# novadac.net
KiCad netlist of a schematic drawn in EasyEDA Pro
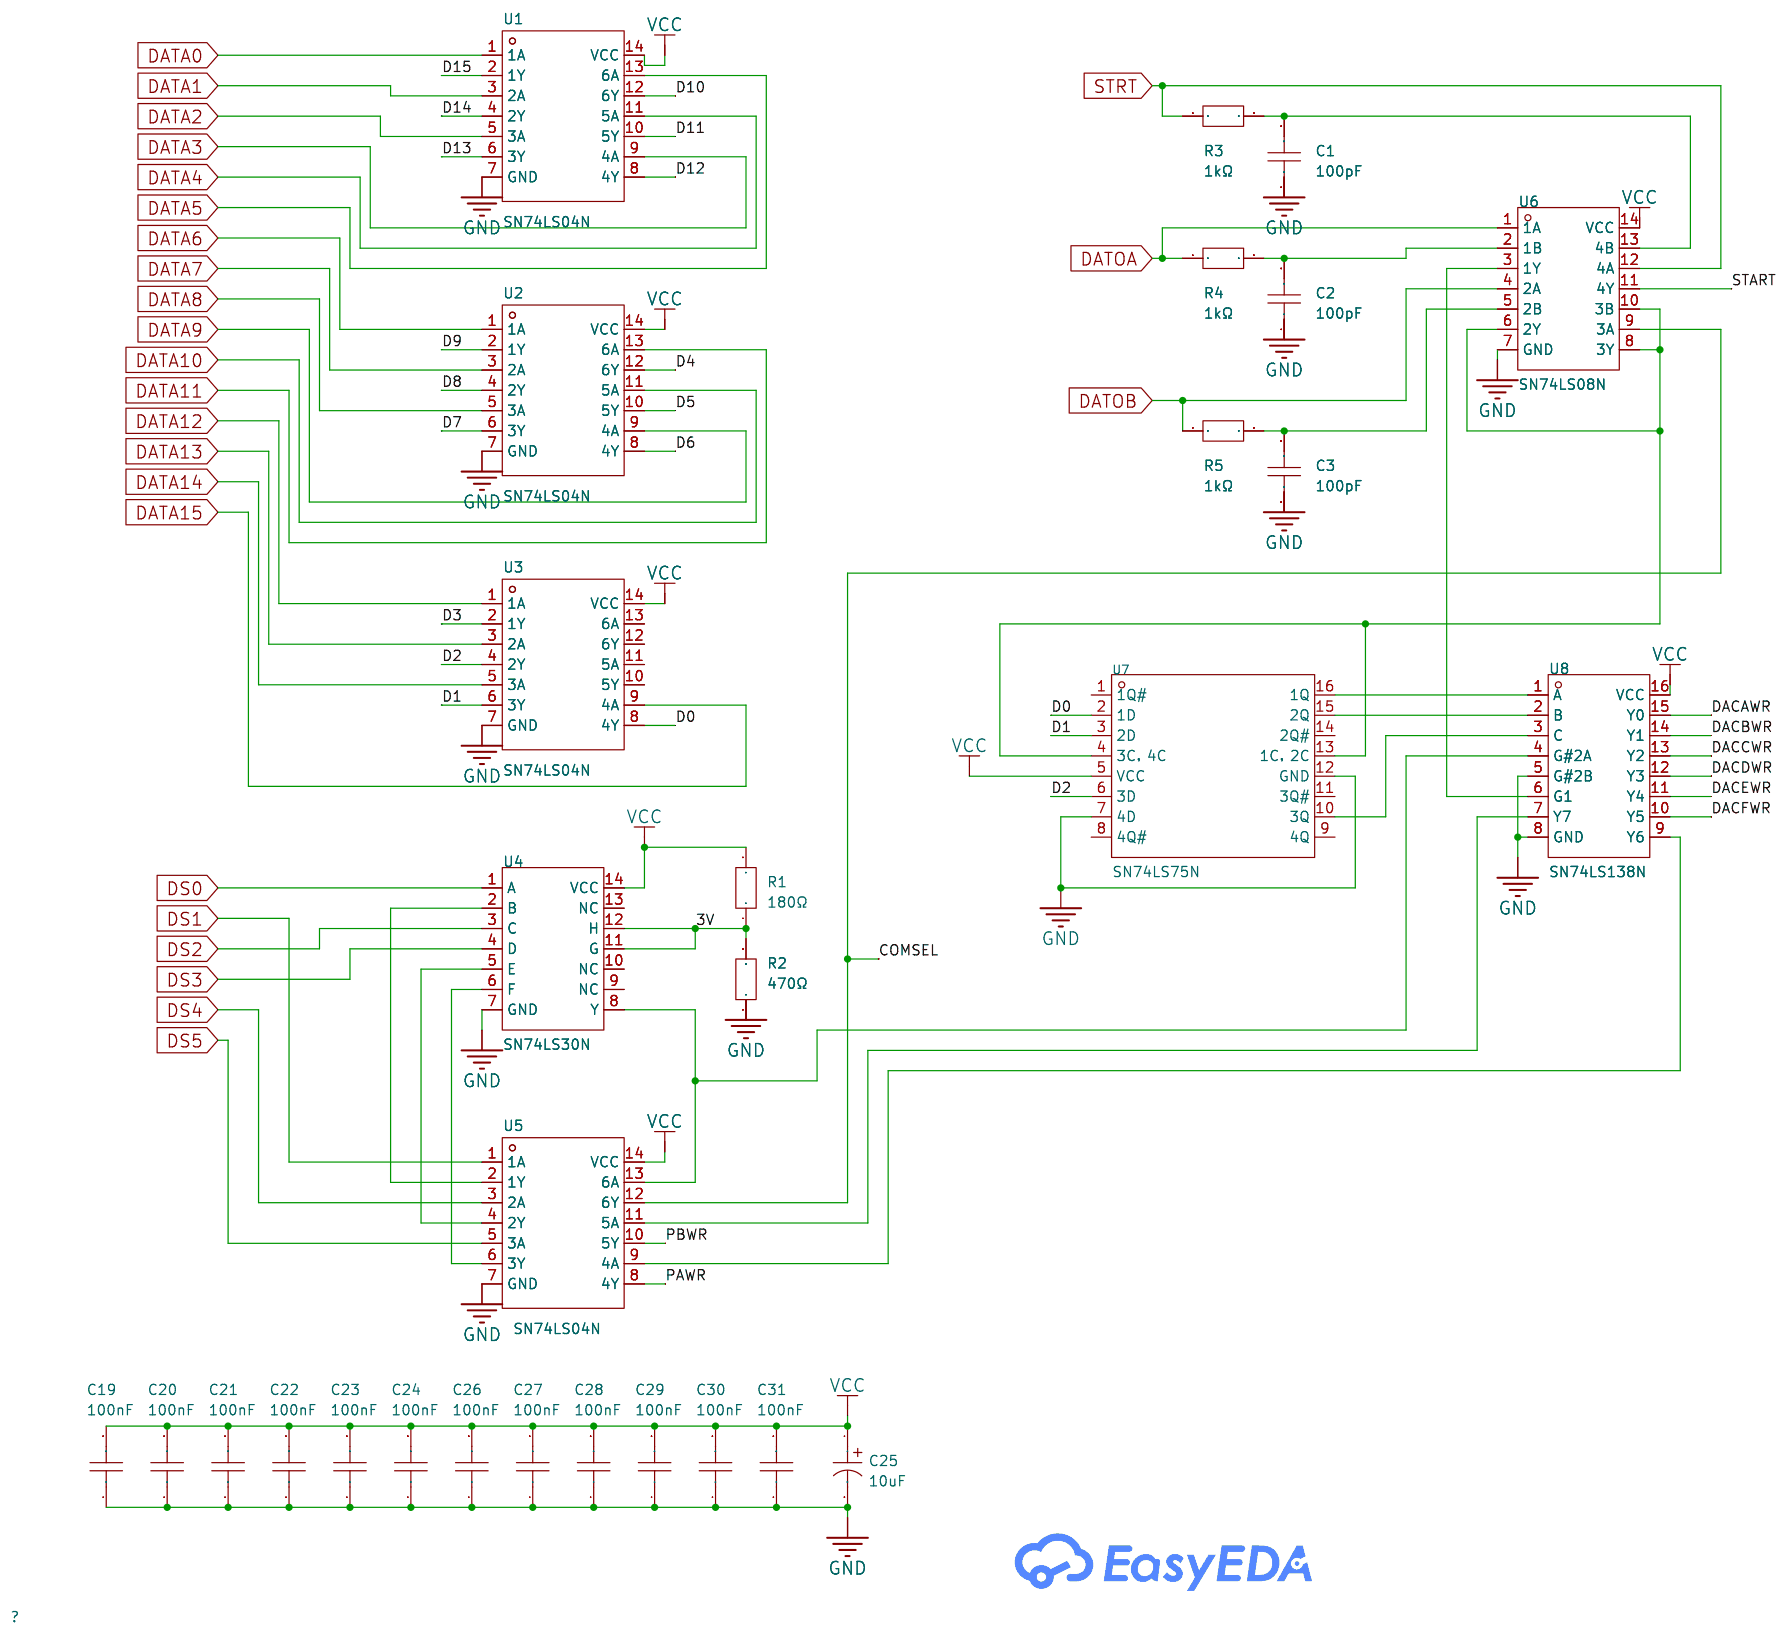
[diagram p0: P1]
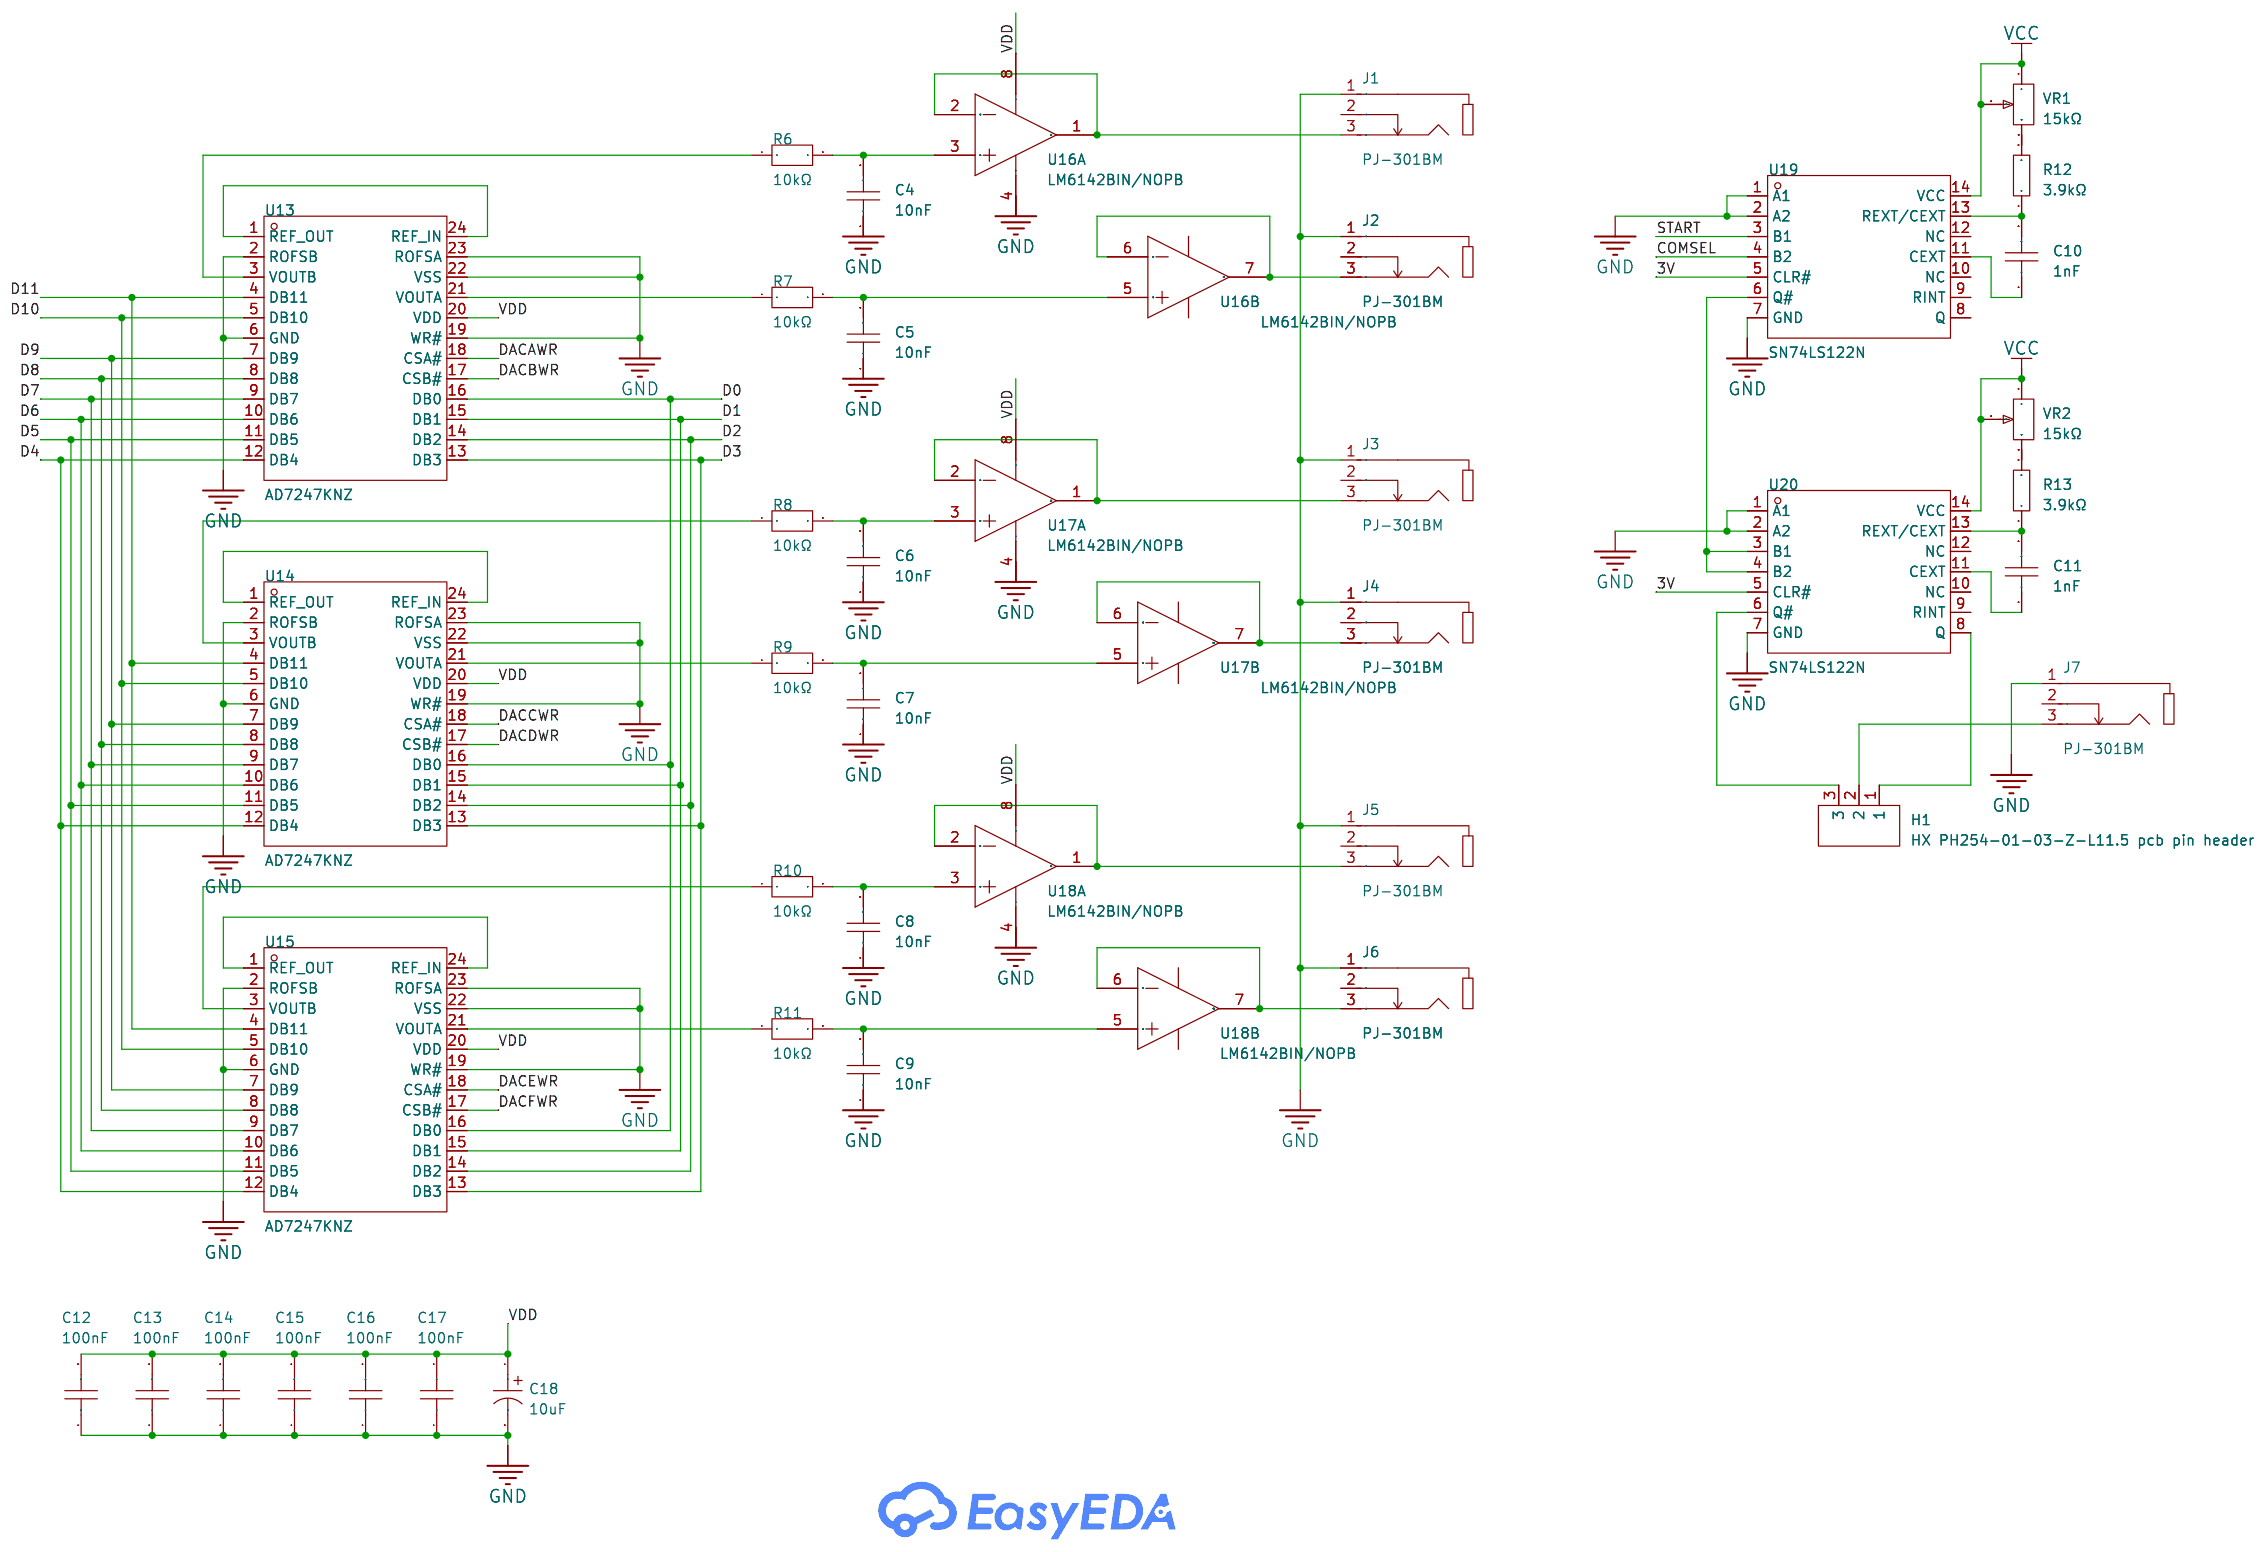
[diagram p1: P2]
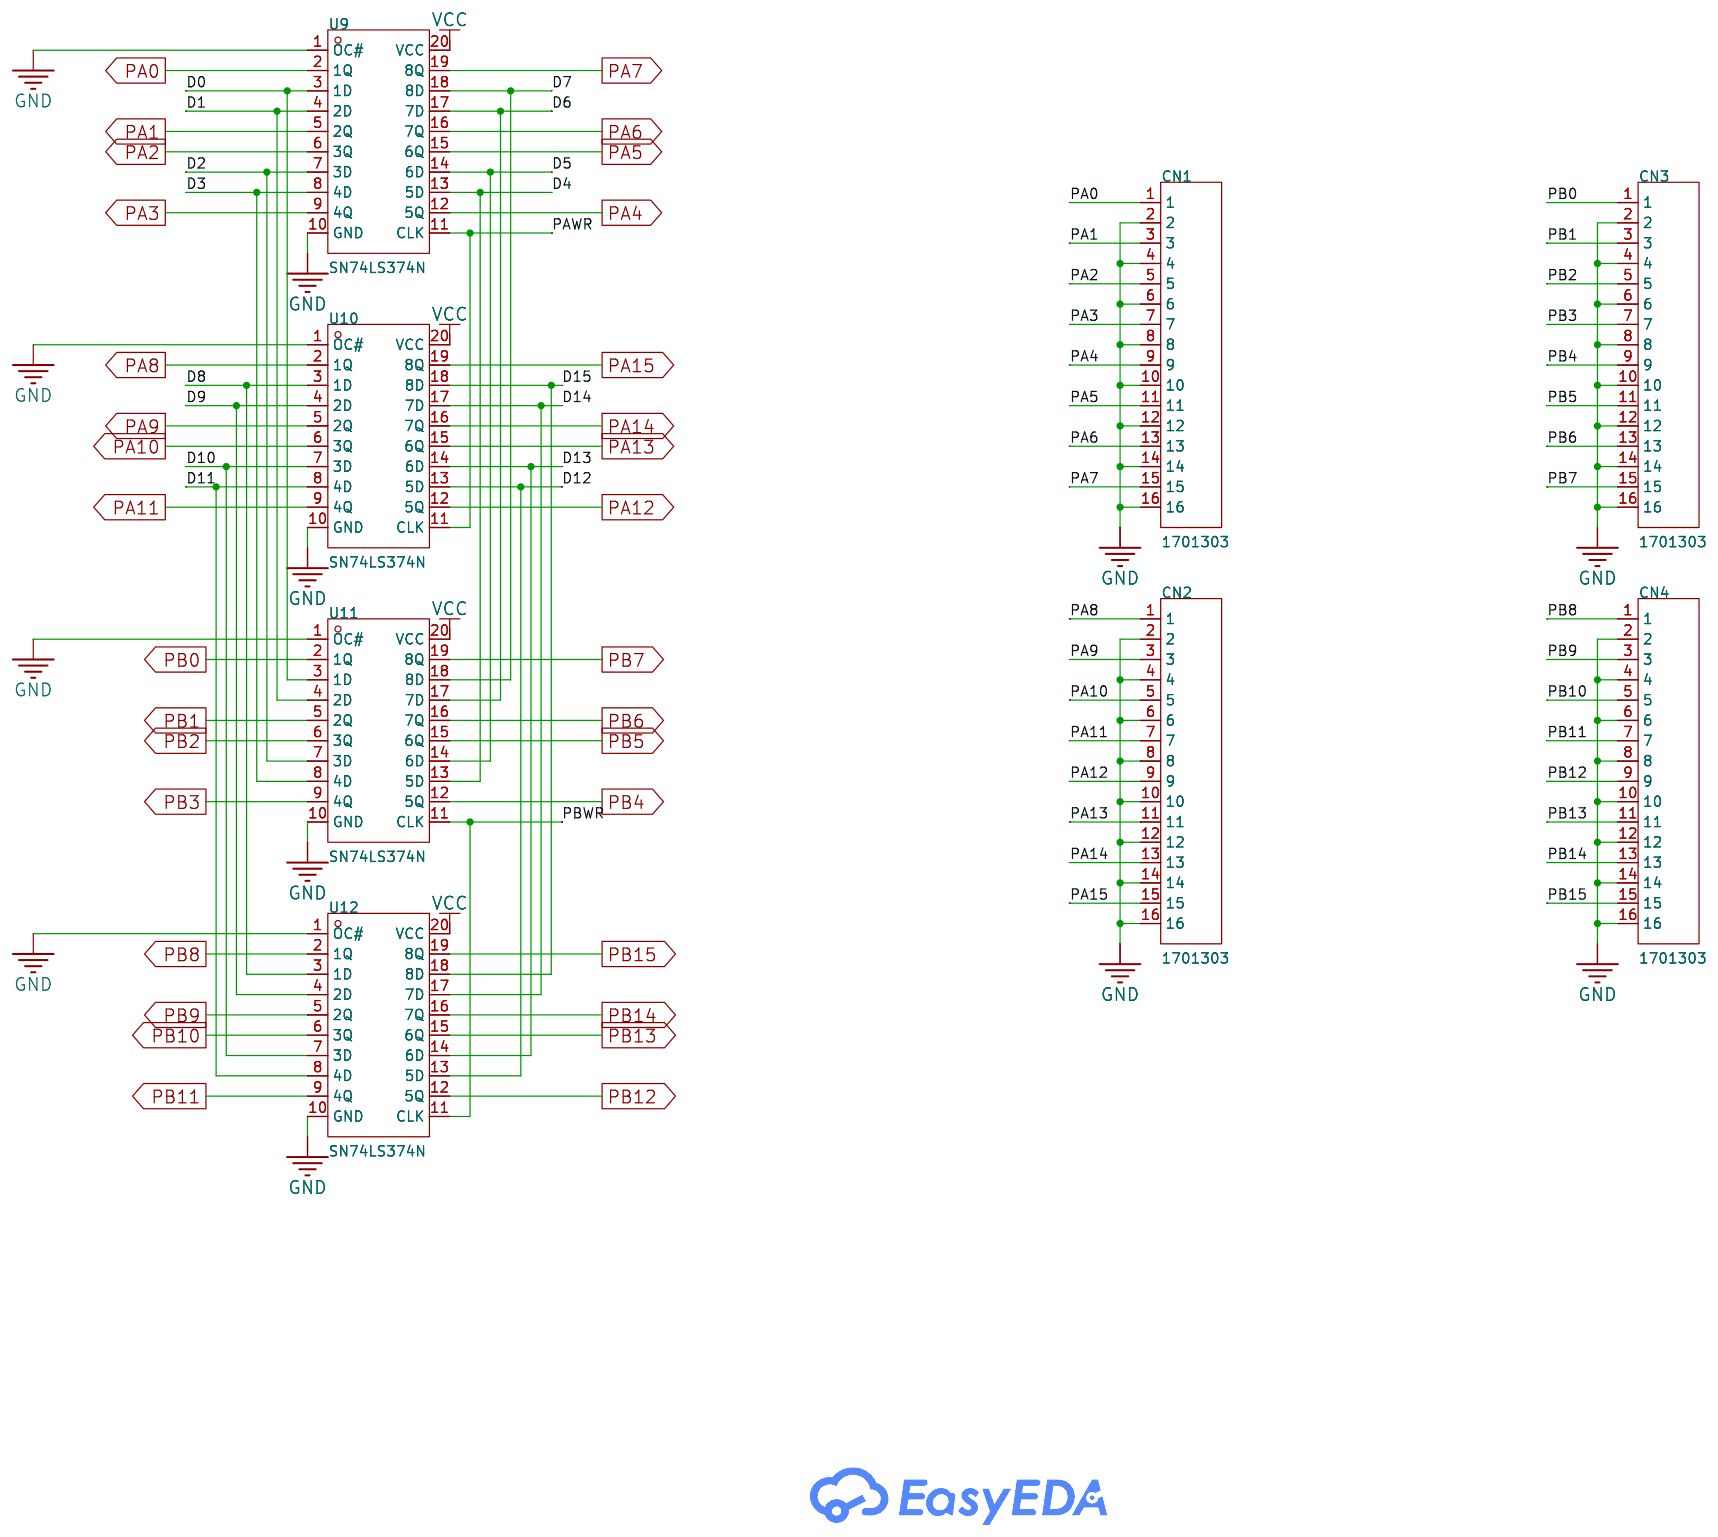
[diagram p2: P3]

(export (version "E")
  (design (tool "Eeschema 10.0.6"))
  (components
    (comp (ref "C1")
      (value "100pF")
      (footprint "easyedapro:CAP-TH_L6.3-W2.6-P5.08-D0.5")
      (fields
        (field (name "Manufacturer Part") "CC1H101JC14DSL6B1100")
        (field (name "Manufacturer") "Dersonic(德尔创)")
      )
      (libsource (lib "easyedapro") (part "CC1H101JC14DSL6B1100"))
    )
    (comp (ref "C2")
      (value "100pF")
      (footprint "easyedapro:CAP-TH_L6.3-W2.6-P5.08-D0.5")
      (fields
        (field (name "Manufacturer Part") "CC1H101JC14DSL6B1100")
        (field (name "Manufacturer") "Dersonic(德尔创)")
      )
      (libsource (lib "easyedapro") (part "CC1H101JC14DSL6B1100"))
    )
    (comp (ref "C3")
      (value "100pF")
      (footprint "easyedapro:CAP-TH_L6.3-W2.6-P5.08-D0.5")
      (fields
        (field (name "Manufacturer Part") "CC1H101JC14DSL6B1100")
        (field (name "Manufacturer") "Dersonic(德尔创)")
      )
      (libsource (lib "easyedapro") (part "CC1H101JC14DSL6B1100"))
    )
    (comp (ref "C19")
      (value "100nF")
      (footprint "easyedapro:CAP-TH_L6.5-W4.0-P5.00-D0.6-S1.20")
      (fields
        (field (name "Manufacturer Part") "DCS104Z26Y5VF6FJ5A0")
        (field (name "Manufacturer") "SHM(南方宏明)")
      )
      (libsource (lib "easyedapro") (part "DCS104Z26Y5VF6FJ5A0"))
    )
    (comp (ref "C20")
      (value "100nF")
      (footprint "easyedapro:CAP-TH_L6.5-W4.0-P5.00-D0.6-S1.20")
      (fields
        (field (name "Manufacturer Part") "DCS104Z26Y5VF6FJ5A0")
        (field (name "Manufacturer") "SHM(南方宏明)")
      )
      (libsource (lib "easyedapro") (part "DCS104Z26Y5VF6FJ5A0"))
    )
    (comp (ref "C21")
      (value "100nF")
      (footprint "easyedapro:CAP-TH_L6.5-W4.0-P5.00-D0.6-S1.20")
      (fields
        (field (name "Manufacturer Part") "DCS104Z26Y5VF6FJ5A0")
        (field (name "Manufacturer") "SHM(南方宏明)")
      )
      (libsource (lib "easyedapro") (part "DCS104Z26Y5VF6FJ5A0"))
    )
    (comp (ref "C22")
      (value "100nF")
      (footprint "easyedapro:CAP-TH_L6.5-W4.0-P5.00-D0.6-S1.20")
      (fields
        (field (name "Manufacturer Part") "DCS104Z26Y5VF6FJ5A0")
        (field (name "Manufacturer") "SHM(南方宏明)")
      )
      (libsource (lib "easyedapro") (part "DCS104Z26Y5VF6FJ5A0"))
    )
    (comp (ref "C23")
      (value "100nF")
      (footprint "easyedapro:CAP-TH_L6.5-W4.0-P5.00-D0.6-S1.20")
      (fields
        (field (name "Manufacturer Part") "DCS104Z26Y5VF6FJ5A0")
        (field (name "Manufacturer") "SHM(南方宏明)")
      )
      (libsource (lib "easyedapro") (part "DCS104Z26Y5VF6FJ5A0"))
    )
    (comp (ref "C24")
      (value "100nF")
      (footprint "easyedapro:CAP-TH_L6.5-W4.0-P5.00-D0.6-S1.20")
      (fields
        (field (name "Manufacturer Part") "DCS104Z26Y5VF6FJ5A0")
        (field (name "Manufacturer") "SHM(南方宏明)")
      )
      (libsource (lib "easyedapro") (part "DCS104Z26Y5VF6FJ5A0"))
    )
    (comp (ref "C25")
      (value "10uF")
      (footprint "easyedapro:CAP-TH_BD5.0-P2.00-D0.5-FD")
      (fields (field (name "Manufacturer Part") "ECA-1HHG100I") (field (name "Manufacturer") "PANASONIC(松下)"))
      (libsource (lib "easyedapro") (part "ECA-1HHG100I"))
    )
    (comp (ref "C26")
      (value "100nF")
      (footprint "easyedapro:CAP-TH_L6.5-W4.0-P5.00-D0.6-S1.20")
      (fields
        (field (name "Manufacturer Part") "DCS104Z26Y5VF6FJ5A0")
        (field (name "Manufacturer") "SHM(南方宏明)")
      )
      (libsource (lib "easyedapro") (part "DCS104Z26Y5VF6FJ5A0"))
    )
    (comp (ref "C27")
      (value "100nF")
      (footprint "easyedapro:CAP-TH_L6.5-W4.0-P5.00-D0.6-S1.20")
      (fields
        (field (name "Manufacturer Part") "DCS104Z26Y5VF6FJ5A0")
        (field (name "Manufacturer") "SHM(南方宏明)")
      )
      (libsource (lib "easyedapro") (part "DCS104Z26Y5VF6FJ5A0"))
    )
    (comp (ref "C28")
      (value "100nF")
      (footprint "easyedapro:CAP-TH_L6.5-W4.0-P5.00-D0.6-S1.20")
      (fields
        (field (name "Manufacturer Part") "DCS104Z26Y5VF6FJ5A0")
        (field (name "Manufacturer") "SHM(南方宏明)")
      )
      (libsource (lib "easyedapro") (part "DCS104Z26Y5VF6FJ5A0"))
    )
    (comp (ref "C29")
      (value "100nF")
      (footprint "easyedapro:CAP-TH_L6.5-W4.0-P5.00-D0.6-S1.20")
      (fields
        (field (name "Manufacturer Part") "DCS104Z26Y5VF6FJ5A0")
        (field (name "Manufacturer") "SHM(南方宏明)")
      )
      (libsource (lib "easyedapro") (part "DCS104Z26Y5VF6FJ5A0"))
    )
    (comp (ref "C30")
      (value "100nF")
      (footprint "easyedapro:CAP-TH_L6.5-W4.0-P5.00-D0.6-S1.20")
      (fields
        (field (name "Manufacturer Part") "DCS104Z26Y5VF6FJ5A0")
        (field (name "Manufacturer") "SHM(南方宏明)")
      )
      (libsource (lib "easyedapro") (part "DCS104Z26Y5VF6FJ5A0"))
    )
    (comp (ref "C31")
      (value "100nF")
      (footprint "easyedapro:CAP-TH_L6.5-W4.0-P5.00-D0.6-S1.20")
      (fields
        (field (name "Manufacturer Part") "DCS104Z26Y5VF6FJ5A0")
        (field (name "Manufacturer") "SHM(南方宏明)")
      )
      (libsource (lib "easyedapro") (part "DCS104Z26Y5VF6FJ5A0"))
    )
    (comp (ref "R1")
      (value "180Ω")
      (footprint "easyedapro:RES-TH_BD2.3-L6.0-P10.00-D0.4")
      (fields
        (field (name "Manufacturer Part") "CF14JT180R")
        (field (name "Manufacturer") "SEI(Stackpole Electronics Inc.)")
      )
      (libsource (lib "easyedapro") (part "CF14JT180R"))
    )
    (comp (ref "R2")
      (value "470Ω")
      (footprint "easyedapro:RES-TH_BD2.5-L6.8-P10.50-D0.5")
      (fields (field (name "Manufacturer Part") "OK4715E-R52") (field (name "Manufacturer") "Ohmite"))
      (libsource (lib "easyedapro") (part "OK4715E-R52"))
    )
    (comp (ref "R3")
      (value "1kΩ")
      (footprint "easyedapro:RES-TH_BD2.4-L6.5-P10.50-D0.5")
      (fields
        (field (name "Manufacturer Part") "PRNF14FTD1K00")
        (field (name "Manufacturer") "SEI(Stackpole Electronics Inc.)")
      )
      (libsource (lib "easyedapro") (part "PRNF14FTD1K00"))
    )
    (comp (ref "R4")
      (value "1kΩ")
      (footprint "easyedapro:RES-TH_BD2.4-L6.5-P10.50-D0.5")
      (fields
        (field (name "Manufacturer Part") "PRNF14FTD1K00")
        (field (name "Manufacturer") "SEI(Stackpole Electronics Inc.)")
      )
      (libsource (lib "easyedapro") (part "PRNF14FTD1K00"))
    )
    (comp (ref "R5")
      (value "1kΩ")
      (footprint "easyedapro:RES-TH_BD2.4-L6.5-P10.50-D0.5")
      (fields
        (field (name "Manufacturer Part") "PRNF14FTD1K00")
        (field (name "Manufacturer") "SEI(Stackpole Electronics Inc.)")
      )
      (libsource (lib "easyedapro") (part "PRNF14FTD1K00"))
    )
    (comp (ref "U1")
      (value "SN74LS04N")
      (footprint "easyedapro:PDIP-14_L19.7-W6.6-P2.54-LS8.3-BL")
      (fields (field (name "Manufacturer") "TI(德州仪器)"))
      (libsource (lib "easyedapro") (part "SN74LS04N"))
    )
    (comp (ref "U2")
      (value "SN74LS04N")
      (footprint "easyedapro:PDIP-14_L19.7-W6.6-P2.54-LS8.3-BL")
      (fields (field (name "Manufacturer") "TI(德州仪器)"))
      (libsource (lib "easyedapro") (part "SN74LS04N"))
    )
    (comp (ref "U3")
      (value "SN74LS04N")
      (footprint "easyedapro:PDIP-14_L19.7-W6.6-P2.54-LS8.3-BL")
      (fields (field (name "Manufacturer") "TI(德州仪器)"))
      (libsource (lib "easyedapro") (part "SN74LS04N"))
    )
    (comp (ref "U4")
      (value "SN74LS30N")
      (footprint "easyedapro:PDIP-14_L19.6-W6.5-P2.54-LS7.9-BL")
      (fields (field (name "Manufacturer") "TI(德州仪器)"))
      (libsource (lib "easyedapro") (part "SN74LS30N"))
    )
    (comp (ref "U5")
      (value "SN74LS04N")
      (footprint "easyedapro:PDIP-14_L19.7-W6.6-P2.54-LS8.3-BL")
      (fields (field (name "Manufacturer") "TI(德州仪器)"))
      (libsource (lib "easyedapro") (part "SN74LS04N"))
    )
    (comp (ref "U6")
      (value "SN74LS08N")
      (footprint "easyedapro:PDIP-14_L19.3-W6.4-P2.54-LS7.9-BL-1")
      (fields (field (name "Manufacturer") "TI(德州仪器)"))
      (libsource (lib "easyedapro") (part "SN74LS08N"))
    )
    (comp (ref "U7")
      (value "SN74LS75N")
      (footprint "easyedapro:DIP-16_L20.0-W6.4-P2.54-LS7.6-BL")
      (fields (field (name "Manufacturer") "TI(德州仪器)"))
      (libsource (lib "easyedapro") (part "SN74LS75N"))
    )
    (comp (ref "U8")
      (value "SN74LS138N")
      (footprint "easyedapro:DIP-16_L19.8-W6.5-P2.54-LS7.6-BL")
      (fields (field (name "Manufacturer") "TI(德州仪器)"))
      (libsource (lib "easyedapro") (part "SN74LS138N"))
    )
    (comp (ref "C4")
      (value "10nF")
      (footprint "easyedapro:CAP-TH_L12.0-W5.0-P7.50-D0.6")
      (fields (field (name "Manufacturer Part") "CT81-M12Y5V1D103MSE") (field (name "Manufacturer") "FH(风华)"))
      (libsource (lib "easyedapro") (part "CT81-M12Y5V1D103MSE"))
    )
    (comp (ref "C5")
      (value "10nF")
      (footprint "easyedapro:CAP-TH_L12.0-W5.0-P7.50-D0.6")
      (fields (field (name "Manufacturer Part") "CT81-M12Y5V1D103MSE") (field (name "Manufacturer") "FH(风华)"))
      (libsource (lib "easyedapro") (part "CT81-M12Y5V1D103MSE"))
    )
    (comp (ref "C6")
      (value "10nF")
      (footprint "easyedapro:CAP-TH_L12.0-W5.0-P7.50-D0.6")
      (fields (field (name "Manufacturer Part") "CT81-M12Y5V1D103MSE") (field (name "Manufacturer") "FH(风华)"))
      (libsource (lib "easyedapro") (part "CT81-M12Y5V1D103MSE"))
    )
    (comp (ref "C7")
      (value "10nF")
      (footprint "easyedapro:CAP-TH_L12.0-W5.0-P7.50-D0.6")
      (fields (field (name "Manufacturer Part") "CT81-M12Y5V1D103MSE") (field (name "Manufacturer") "FH(风华)"))
      (libsource (lib "easyedapro") (part "CT81-M12Y5V1D103MSE"))
    )
    (comp (ref "C8")
      (value "10nF")
      (footprint "easyedapro:CAP-TH_L12.0-W5.0-P7.50-D0.6")
      (fields (field (name "Manufacturer Part") "CT81-M12Y5V1D103MSE") (field (name "Manufacturer") "FH(风华)"))
      (libsource (lib "easyedapro") (part "CT81-M12Y5V1D103MSE"))
    )
    (comp (ref "C9")
      (value "10nF")
      (footprint "easyedapro:CAP-TH_L12.0-W5.0-P7.50-D0.6")
      (fields (field (name "Manufacturer Part") "CT81-M12Y5V1D103MSE") (field (name "Manufacturer") "FH(风华)"))
      (libsource (lib "easyedapro") (part "CT81-M12Y5V1D103MSE"))
    )
    (comp (ref "C10")
      (value "1nF")
      (footprint "easyedapro:CAP-TH_L8.4-W5.0-P6.40-D0.8-S2.5")
      (fields (field (name "Manufacturer Part") "564R30GAD10") (field (name "Manufacturer") "VISHAY(威世)"))
      (libsource (lib "easyedapro") (part "564R30GAD10"))
    )
    (comp (ref "C11")
      (value "1nF")
      (footprint "easyedapro:CAP-TH_L8.4-W5.0-P6.40-D0.8-S2.5")
      (fields (field (name "Manufacturer Part") "564R30GAD10") (field (name "Manufacturer") "VISHAY(威世)"))
      (libsource (lib "easyedapro") (part "564R30GAD10"))
    )
    (comp (ref "C12")
      (value "100nF")
      (footprint "easyedapro:CAP-TH_L6.5-W4.0-P5.00-D0.6-S1.20")
      (fields
        (field (name "Manufacturer Part") "DCS104Z26Y5VF6FJ5A0")
        (field (name "Manufacturer") "SHM(南方宏明)")
      )
      (libsource (lib "easyedapro") (part "DCS104Z26Y5VF6FJ5A0"))
    )
    (comp (ref "C13")
      (value "100nF")
      (footprint "easyedapro:CAP-TH_L6.5-W4.0-P5.00-D0.6-S1.20")
      (fields
        (field (name "Manufacturer Part") "DCS104Z26Y5VF6FJ5A0")
        (field (name "Manufacturer") "SHM(南方宏明)")
      )
      (libsource (lib "easyedapro") (part "DCS104Z26Y5VF6FJ5A0"))
    )
    (comp (ref "C14")
      (value "100nF")
      (footprint "easyedapro:CAP-TH_L6.5-W4.0-P5.00-D0.6-S1.20")
      (fields
        (field (name "Manufacturer Part") "DCS104Z26Y5VF6FJ5A0")
        (field (name "Manufacturer") "SHM(南方宏明)")
      )
      (libsource (lib "easyedapro") (part "DCS104Z26Y5VF6FJ5A0"))
    )
    (comp (ref "C15")
      (value "100nF")
      (footprint "easyedapro:CAP-TH_L6.5-W4.0-P5.00-D0.6-S1.20")
      (fields
        (field (name "Manufacturer Part") "DCS104Z26Y5VF6FJ5A0")
        (field (name "Manufacturer") "SHM(南方宏明)")
      )
      (libsource (lib "easyedapro") (part "DCS104Z26Y5VF6FJ5A0"))
    )
    (comp (ref "C16")
      (value "100nF")
      (footprint "easyedapro:CAP-TH_L6.5-W4.0-P5.00-D0.6-S1.20")
      (fields
        (field (name "Manufacturer Part") "DCS104Z26Y5VF6FJ5A0")
        (field (name "Manufacturer") "SHM(南方宏明)")
      )
      (libsource (lib "easyedapro") (part "DCS104Z26Y5VF6FJ5A0"))
    )
    (comp (ref "C17")
      (value "100nF")
      (footprint "easyedapro:CAP-TH_L6.5-W4.0-P5.00-D0.6-S1.20")
      (fields
        (field (name "Manufacturer Part") "DCS104Z26Y5VF6FJ5A0")
        (field (name "Manufacturer") "SHM(南方宏明)")
      )
      (libsource (lib "easyedapro") (part "DCS104Z26Y5VF6FJ5A0"))
    )
    (comp (ref "C18")
      (value "10uF")
      (footprint "easyedapro:CAP-TH_BD5.0-P2.00-D0.5-FD")
      (fields (field (name "Manufacturer Part") "ECA-1HHG100I") (field (name "Manufacturer") "PANASONIC(松下)"))
      (libsource (lib "easyedapro") (part "ECA-1HHG100I"))
    )
    (comp (ref "H1")
      (value "HX PH254-01-03-Z-L11.5 pcb pin header")
      (footprint "easyedapro:HDR-TH_3P-P2.54-V-M-1")
      (fields (field (name "Manufacturer") "hanxia(韩下)"))
      (libsource (lib "easyedapro") (part "HX PH254-01-03-Z-L11.5 PCB PIN HEADER"))
    )
    (comp (ref "J1")
      (value "PJ-301BM")
      (footprint "easyedapro:AUDIO-TH_PJ-301BM")
      (libsource (lib "easyedapro") (part "PJ-301BM"))
    )
    (comp (ref "J2")
      (value "PJ-301BM")
      (footprint "easyedapro:AUDIO-TH_PJ-301BM")
      (libsource (lib "easyedapro") (part "PJ-301BM"))
    )
    (comp (ref "J3")
      (value "PJ-301BM")
      (footprint "easyedapro:AUDIO-TH_PJ-301BM")
      (libsource (lib "easyedapro") (part "PJ-301BM"))
    )
    (comp (ref "J4")
      (value "PJ-301BM")
      (footprint "easyedapro:AUDIO-TH_PJ-301BM")
      (libsource (lib "easyedapro") (part "PJ-301BM"))
    )
    (comp (ref "J5")
      (value "PJ-301BM")
      (footprint "easyedapro:AUDIO-TH_PJ-301BM")
      (libsource (lib "easyedapro") (part "PJ-301BM"))
    )
    (comp (ref "J6")
      (value "PJ-301BM")
      (footprint "easyedapro:AUDIO-TH_PJ-301BM")
      (libsource (lib "easyedapro") (part "PJ-301BM"))
    )
    (comp (ref "J7")
      (value "PJ-301BM")
      (footprint "easyedapro:AUDIO-TH_PJ-301BM")
      (libsource (lib "easyedapro") (part "PJ-301BM"))
    )
    (comp (ref "R6")
      (value "10kΩ")
      (footprint "easyedapro:RES-TH_BD2.3-L6.0-P10.00-D0.6")
      (fields
        (field (name "Manufacturer Part") "PCF14JA4K70")
        (field (name "Manufacturer") "SEI(Stackpole Electronics Inc.)")
      )
      (libsource (lib "easyedapro") (part "PCF14JA4K70"))
    )
    (comp (ref "R7")
      (value "10kΩ")
      (footprint "easyedapro:RES-TH_BD2.3-L6.0-P10.00-D0.6")
      (fields
        (field (name "Manufacturer Part") "PCF14JA4K70")
        (field (name "Manufacturer") "SEI(Stackpole Electronics Inc.)")
      )
      (libsource (lib "easyedapro") (part "PCF14JA4K70"))
    )
    (comp (ref "R8")
      (value "10kΩ")
      (footprint "easyedapro:RES-TH_BD2.3-L6.0-P10.00-D0.6")
      (fields
        (field (name "Manufacturer Part") "PCF14JA4K70")
        (field (name "Manufacturer") "SEI(Stackpole Electronics Inc.)")
      )
      (libsource (lib "easyedapro") (part "PCF14JA4K70"))
    )
    (comp (ref "R9")
      (value "10kΩ")
      (footprint "easyedapro:RES-TH_BD2.3-L6.0-P10.00-D0.6")
      (fields
        (field (name "Manufacturer Part") "PCF14JA4K70")
        (field (name "Manufacturer") "SEI(Stackpole Electronics Inc.)")
      )
      (libsource (lib "easyedapro") (part "PCF14JA4K70"))
    )
    (comp (ref "R10")
      (value "10kΩ")
      (footprint "easyedapro:RES-TH_BD2.3-L6.0-P10.00-D0.6")
      (fields
        (field (name "Manufacturer Part") "PCF14JA4K70")
        (field (name "Manufacturer") "SEI(Stackpole Electronics Inc.)")
      )
      (libsource (lib "easyedapro") (part "PCF14JA4K70"))
    )
    (comp (ref "R11")
      (value "10kΩ")
      (footprint "easyedapro:RES-TH_BD2.3-L6.0-P10.00-D0.6")
      (fields
        (field (name "Manufacturer Part") "PCF14JA4K70")
        (field (name "Manufacturer") "SEI(Stackpole Electronics Inc.)")
      )
      (libsource (lib "easyedapro") (part "PCF14JA4K70"))
    )
    (comp (ref "R12")
      (value "3.9kΩ")
      (footprint "easyedapro:RES-TH_BD2.2-L6.5-P10.50-D0.6")
      (fields (field (name "Manufacturer Part") "MFR-25FTE52-3K9") (field (name "Manufacturer") "YAGEO(国巨)"))
      (libsource (lib "easyedapro") (part "MFR-25FTE52-3K9"))
    )
    (comp (ref "R13")
      (value "3.9kΩ")
      (footprint "easyedapro:RES-TH_BD2.2-L6.5-P10.50-D0.6")
      (fields (field (name "Manufacturer Part") "MFR-25FTE52-3K9") (field (name "Manufacturer") "YAGEO(国巨)"))
      (libsource (lib "easyedapro") (part "MFR-25FTE52-3K9"))
    )
    (comp (ref "U13")
      (value "AD7247KNZ")
      (footprint "easyedapro:PDIP-24_L32.5-W6.5-P2.54-LS7.9-BL")
      (fields (field (name "Manufacturer") "ADI(亚德诺)"))
      (libsource (lib "easyedapro") (part "AD7247KNZ"))
    )
    (comp (ref "U14")
      (value "AD7247KNZ")
      (footprint "easyedapro:PDIP-24_L32.5-W6.5-P2.54-LS7.9-BL")
      (fields (field (name "Manufacturer") "ADI(亚德诺)"))
      (libsource (lib "easyedapro") (part "AD7247KNZ"))
    )
    (comp (ref "U15")
      (value "AD7247KNZ")
      (footprint "easyedapro:PDIP-24_L32.5-W6.5-P2.54-LS7.9-BL")
      (fields (field (name "Manufacturer") "ADI(亚德诺)"))
      (libsource (lib "easyedapro") (part "AD7247KNZ"))
    )
    (comp (ref "U16")
      (value "LM6142BIN/NOPB")
      (footprint "easyedapro:PDIP-8_L9.6-W6.4-P2.54-LS7.9-BL")
      (fields (field (name "Manufacturer") "TI(德州仪器)"))
      (libsource (lib "easyedapro") (part "LM6142BIN/NOPB"))
    )
    (comp (ref "U17")
      (value "LM6142BIN/NOPB")
      (footprint "easyedapro:PDIP-8_L9.6-W6.4-P2.54-LS7.9-BL")
      (fields (field (name "Manufacturer") "TI(德州仪器)"))
      (libsource (lib "easyedapro") (part "LM6142BIN/NOPB"))
    )
    (comp (ref "U18")
      (value "LM6142BIN/NOPB")
      (footprint "easyedapro:PDIP-8_L9.6-W6.4-P2.54-LS7.9-BL")
      (fields (field (name "Manufacturer") "TI(德州仪器)"))
      (libsource (lib "easyedapro") (part "LM6142BIN/NOPB"))
    )
    (comp (ref "U19")
      (value "SN74LS122N")
      (footprint "easyedapro:PDIP-14_L19.2-W6.6-P2.54-LS7.6-BL")
      (fields (field (name "Manufacturer") "TI(德州仪器)"))
      (libsource (lib "easyedapro") (part "SN74LS122N"))
    )
    (comp (ref "U20")
      (value "SN74LS122N")
      (footprint "easyedapro:PDIP-14_L19.2-W6.6-P2.54-LS7.6-BL")
      (fields (field (name "Manufacturer") "TI(德州仪器)"))
      (libsource (lib "easyedapro") (part "SN74LS122N"))
    )
    (comp (ref "VR1")
      (value "15kΩ")
      (footprint "easyedapro:RES-ADJ-TH_3362P")
      (fields (field (name "Manufacturer Part") "3362P-1-103LF") (field (name "Manufacturer") "BOURNS"))
      (libsource (lib "easyedapro") (part "3362P-1-103LF"))
    )
    (comp (ref "VR2")
      (value "15kΩ")
      (footprint "easyedapro:RES-ADJ-TH_3362P")
      (fields (field (name "Manufacturer Part") "3362P-1-103LF") (field (name "Manufacturer") "BOURNS"))
      (libsource (lib "easyedapro") (part "3362P-1-103LF"))
    )
    (comp (ref "CN1")
      (value "1701303")
      (footprint "easyedapro:CONN-TH_1701303")
      (fields (field (name "Manufacturer") "Phoenix Contact(菲尼克斯)"))
      (libsource (lib "easyedapro") (part "1701303"))
    )
    (comp (ref "CN2")
      (value "1701303")
      (footprint "easyedapro:CONN-TH_1701303")
      (fields (field (name "Manufacturer") "Phoenix Contact(菲尼克斯)"))
      (libsource (lib "easyedapro") (part "1701303"))
    )
    (comp (ref "CN3")
      (value "1701303")
      (footprint "easyedapro:CONN-TH_1701303")
      (fields (field (name "Manufacturer") "Phoenix Contact(菲尼克斯)"))
      (libsource (lib "easyedapro") (part "1701303"))
    )
    (comp (ref "CN4")
      (value "1701303")
      (footprint "easyedapro:CONN-TH_1701303")
      (fields (field (name "Manufacturer") "Phoenix Contact(菲尼克斯)"))
      (libsource (lib "easyedapro") (part "1701303"))
    )
    (comp (ref "U9")
      (value "SN74LS374N")
      (footprint "easyedapro:PDIP-20_L25.4-W6.4-P2.54-LS7.6-BL")
      (fields (field (name "Manufacturer") "TI(德州仪器)"))
      (libsource (lib "easyedapro") (part "SN74LS374N"))
    )
    (comp (ref "U10")
      (value "SN74LS374N")
      (footprint "easyedapro:PDIP-20_L25.4-W6.4-P2.54-LS7.6-BL")
      (fields (field (name "Manufacturer") "TI(德州仪器)"))
      (libsource (lib "easyedapro") (part "SN74LS374N"))
    )
    (comp (ref "U11")
      (value "SN74LS374N")
      (footprint "easyedapro:PDIP-20_L25.4-W6.4-P2.54-LS7.6-BL")
      (fields (field (name "Manufacturer") "TI(德州仪器)"))
      (libsource (lib "easyedapro") (part "SN74LS374N"))
    )
    (comp (ref "U12")
      (value "SN74LS374N")
      (footprint "easyedapro:PDIP-20_L25.4-W6.4-P2.54-LS7.6-BL")
      (fields (field (name "Manufacturer") "TI(德州仪器)"))
      (libsource (lib "easyedapro") (part "SN74LS374N"))
    )
  )
  (nets
    (net (code "1") (name "3V") (class "Default")
      (node (ref "R1") (pin "1") (pinfunction "1_1") (pintype "unspecified"))
      (node (ref "R2") (pin "2") (pinfunction "2_2") (pintype "unspecified"))
      (node (ref "U19") (pin "5") (pinfunction "CLR#_5") (pintype "unspecified"))
      (node (ref "U20") (pin "5") (pinfunction "CLR#_5") (pintype "unspecified"))
      (node (ref "U4") (pin "11") (pinfunction "G_11") (pintype "unspecified"))
      (node (ref "U4") (pin "12") (pinfunction "H_12") (pintype "unspecified"))
    )
    (net (code "2") (name "COMSEL") (class "Default")
      (node (ref "U19") (pin "4") (pinfunction "B2_4") (pintype "unspecified"))
      (node (ref "U5") (pin "12") (pinfunction "6Y_12") (pintype "unspecified"))
      (node (ref "U6") (pin "9") (pinfunction "3A_9") (pintype "unspecified"))
    )
    (net (code "3") (name "D0") (class "Default")
      (node (ref "U11") (pin "3") (pinfunction "1D_3") (pintype "input"))
      (node (ref "U13") (pin "16") (pinfunction "DB0_16") (pintype "unspecified"))
      (node (ref "U14") (pin "16") (pinfunction "DB0_16") (pintype "unspecified"))
      (node (ref "U15") (pin "16") (pinfunction "DB0_16") (pintype "unspecified"))
      (node (ref "U3") (pin "8") (pinfunction "4Y_8") (pintype "unspecified"))
      (node (ref "U7") (pin "2") (pinfunction "1D_2") (pintype "input"))
      (node (ref "U9") (pin "3") (pinfunction "1D_3") (pintype "input"))
    )
    (net (code "4") (name "D1") (class "Default")
      (node (ref "U11") (pin "4") (pinfunction "2D_4") (pintype "input"))
      (node (ref "U13") (pin "15") (pinfunction "DB1_15") (pintype "unspecified"))
      (node (ref "U14") (pin "15") (pinfunction "DB1_15") (pintype "unspecified"))
      (node (ref "U15") (pin "15") (pinfunction "DB1_15") (pintype "unspecified"))
      (node (ref "U3") (pin "6") (pinfunction "3Y_6") (pintype "unspecified"))
      (node (ref "U7") (pin "3") (pinfunction "2D_3") (pintype "input"))
      (node (ref "U9") (pin "4") (pinfunction "2D_4") (pintype "input"))
    )
    (net (code "5") (name "D2") (class "Default")
      (node (ref "U11") (pin "7") (pinfunction "3D_7") (pintype "input"))
      (node (ref "U13") (pin "14") (pinfunction "DB2_14") (pintype "unspecified"))
      (node (ref "U14") (pin "14") (pinfunction "DB2_14") (pintype "unspecified"))
      (node (ref "U15") (pin "14") (pinfunction "DB2_14") (pintype "unspecified"))
      (node (ref "U3") (pin "4") (pinfunction "2Y_4") (pintype "unspecified"))
      (node (ref "U7") (pin "6") (pinfunction "3D_6") (pintype "input"))
      (node (ref "U9") (pin "7") (pinfunction "3D_7") (pintype "input"))
    )
    (net (code "6") (name "D3") (class "Default")
      (node (ref "U11") (pin "8") (pinfunction "4D_8") (pintype "input"))
      (node (ref "U13") (pin "13") (pinfunction "DB3_13") (pintype "unspecified"))
      (node (ref "U14") (pin "13") (pinfunction "DB3_13") (pintype "unspecified"))
      (node (ref "U15") (pin "13") (pinfunction "DB3_13") (pintype "unspecified"))
      (node (ref "U3") (pin "2") (pinfunction "1Y_2") (pintype "unspecified"))
      (node (ref "U9") (pin "8") (pinfunction "4D_8") (pintype "input"))
    )
    (net (code "7") (name "D4") (class "Default")
      (node (ref "U11") (pin "13") (pinfunction "5D_13") (pintype "input"))
      (node (ref "U13") (pin "12") (pinfunction "DB4_12") (pintype "unspecified"))
      (node (ref "U14") (pin "12") (pinfunction "DB4_12") (pintype "unspecified"))
      (node (ref "U15") (pin "12") (pinfunction "DB4_12") (pintype "unspecified"))
      (node (ref "U2") (pin "12") (pinfunction "6Y_12") (pintype "unspecified"))
      (node (ref "U9") (pin "13") (pinfunction "5D_13") (pintype "input"))
    )
    (net (code "8") (name "D5") (class "Default")
      (node (ref "U11") (pin "14") (pinfunction "6D_14") (pintype "input"))
      (node (ref "U13") (pin "11") (pinfunction "DB5_11") (pintype "unspecified"))
      (node (ref "U14") (pin "11") (pinfunction "DB5_11") (pintype "unspecified"))
      (node (ref "U15") (pin "11") (pinfunction "DB5_11") (pintype "unspecified"))
      (node (ref "U2") (pin "10") (pinfunction "5Y_10") (pintype "unspecified"))
      (node (ref "U9") (pin "14") (pinfunction "6D_14") (pintype "input"))
    )
    (net (code "9") (name "D6") (class "Default")
      (node (ref "U11") (pin "17") (pinfunction "7D_17") (pintype "input"))
      (node (ref "U13") (pin "10") (pinfunction "DB6_10") (pintype "unspecified"))
      (node (ref "U14") (pin "10") (pinfunction "DB6_10") (pintype "unspecified"))
      (node (ref "U15") (pin "10") (pinfunction "DB6_10") (pintype "unspecified"))
      (node (ref "U2") (pin "8") (pinfunction "4Y_8") (pintype "unspecified"))
      (node (ref "U9") (pin "17") (pinfunction "7D_17") (pintype "input"))
    )
    (net (code "10") (name "D7") (class "Default")
      (node (ref "U11") (pin "18") (pinfunction "8D_18") (pintype "input"))
      (node (ref "U13") (pin "9") (pinfunction "DB7_9") (pintype "unspecified"))
      (node (ref "U14") (pin "9") (pinfunction "DB7_9") (pintype "unspecified"))
      (node (ref "U15") (pin "9") (pinfunction "DB7_9") (pintype "unspecified"))
      (node (ref "U2") (pin "6") (pinfunction "3Y_6") (pintype "unspecified"))
      (node (ref "U9") (pin "18") (pinfunction "8D_18") (pintype "input"))
    )
    (net (code "11") (name "D8") (class "Default")
      (node (ref "U10") (pin "3") (pinfunction "1D_3") (pintype "input"))
      (node (ref "U12") (pin "3") (pinfunction "1D_3") (pintype "input"))
      (node (ref "U13") (pin "8") (pinfunction "DB8_8") (pintype "unspecified"))
      (node (ref "U14") (pin "8") (pinfunction "DB8_8") (pintype "unspecified"))
      (node (ref "U15") (pin "8") (pinfunction "DB8_8") (pintype "unspecified"))
      (node (ref "U2") (pin "4") (pinfunction "2Y_4") (pintype "unspecified"))
    )
    (net (code "12") (name "D9") (class "Default")
      (node (ref "U10") (pin "4") (pinfunction "2D_4") (pintype "input"))
      (node (ref "U12") (pin "4") (pinfunction "2D_4") (pintype "input"))
      (node (ref "U13") (pin "7") (pinfunction "DB9_7") (pintype "unspecified"))
      (node (ref "U14") (pin "7") (pinfunction "DB9_7") (pintype "unspecified"))
      (node (ref "U15") (pin "7") (pinfunction "DB9_7") (pintype "unspecified"))
      (node (ref "U2") (pin "2") (pinfunction "1Y_2") (pintype "unspecified"))
    )
    (net (code "13") (name "D10") (class "Default")
      (node (ref "U1") (pin "12") (pinfunction "6Y_12") (pintype "unspecified"))
      (node (ref "U10") (pin "7") (pinfunction "3D_7") (pintype "input"))
      (node (ref "U12") (pin "7") (pinfunction "3D_7") (pintype "input"))
      (node (ref "U13") (pin "5") (pinfunction "DB10_5") (pintype "unspecified"))
      (node (ref "U14") (pin "5") (pinfunction "DB10_5") (pintype "unspecified"))
      (node (ref "U15") (pin "5") (pinfunction "DB10_5") (pintype "unspecified"))
    )
    (net (code "14") (name "D11") (class "Default")
      (node (ref "U1") (pin "10") (pinfunction "5Y_10") (pintype "unspecified"))
      (node (ref "U10") (pin "8") (pinfunction "4D_8") (pintype "input"))
      (node (ref "U12") (pin "8") (pinfunction "4D_8") (pintype "input"))
      (node (ref "U13") (pin "4") (pinfunction "DB11_4") (pintype "unspecified"))
      (node (ref "U14") (pin "4") (pinfunction "DB11_4") (pintype "unspecified"))
      (node (ref "U15") (pin "4") (pinfunction "DB11_4") (pintype "unspecified"))
    )
    (net (code "15") (name "D12") (class "Default")
      (node (ref "U1") (pin "8") (pinfunction "4Y_8") (pintype "unspecified"))
      (node (ref "U10") (pin "13") (pinfunction "5D_13") (pintype "input"))
      (node (ref "U12") (pin "13") (pinfunction "5D_13") (pintype "input"))
    )
    (net (code "16") (name "D13") (class "Default")
      (node (ref "U1") (pin "6") (pinfunction "3Y_6") (pintype "unspecified"))
      (node (ref "U10") (pin "14") (pinfunction "6D_14") (pintype "input"))
      (node (ref "U12") (pin "14") (pinfunction "6D_14") (pintype "input"))
    )
    (net (code "17") (name "D14") (class "Default")
      (node (ref "U1") (pin "4") (pinfunction "2Y_4") (pintype "unspecified"))
      (node (ref "U10") (pin "17") (pinfunction "7D_17") (pintype "input"))
      (node (ref "U12") (pin "17") (pinfunction "7D_17") (pintype "input"))
    )
    (net (code "18") (name "D15") (class "Default")
      (node (ref "U1") (pin "2") (pinfunction "1Y_2") (pintype "unspecified"))
      (node (ref "U10") (pin "18") (pinfunction "8D_18") (pintype "input"))
      (node (ref "U12") (pin "18") (pinfunction "8D_18") (pintype "input"))
    )
    (net (code "19") (name "DACAWR") (class "Default")
      (node (ref "U13") (pin "18") (pinfunction "CSA#_18") (pintype "unspecified"))
      (node (ref "U8") (pin "15") (pinfunction "Y0_15") (pintype "input"))
    )
    (net (code "20") (name "DACBWR") (class "Default")
      (node (ref "U13") (pin "17") (pinfunction "CSB#_17") (pintype "unspecified"))
      (node (ref "U8") (pin "14") (pinfunction "Y1_14") (pintype "input"))
    )
    (net (code "21") (name "DACCWR") (class "Default")
      (node (ref "U14") (pin "18") (pinfunction "CSA#_18") (pintype "unspecified"))
      (node (ref "U8") (pin "13") (pinfunction "Y2_13") (pintype "input"))
    )
    (net (code "22") (name "DACDWR") (class "Default")
      (node (ref "U14") (pin "17") (pinfunction "CSB#_17") (pintype "unspecified"))
      (node (ref "U8") (pin "12") (pinfunction "Y3_12") (pintype "input"))
    )
    (net (code "23") (name "DACEWR") (class "Default")
      (node (ref "U15") (pin "18") (pinfunction "CSA#_18") (pintype "unspecified"))
      (node (ref "U8") (pin "11") (pinfunction "Y4_11") (pintype "input"))
    )
    (net (code "24") (name "DACFWR") (class "Default")
      (node (ref "U15") (pin "17") (pinfunction "CSB#_17") (pintype "unspecified"))
      (node (ref "U8") (pin "10") (pinfunction "Y5_10") (pintype "input"))
    )
    (net (code "25") (name "DATA0") (class "Default")
      (node (ref "U1") (pin "1") (pinfunction "1A_1") (pintype "unspecified"))
    )
    (net (code "26") (name "DATA1") (class "Default")
      (node (ref "U1") (pin "3") (pinfunction "2A_3") (pintype "unspecified"))
    )
    (net (code "27") (name "DATA2") (class "Default")
      (node (ref "U1") (pin "5") (pinfunction "3A_5") (pintype "unspecified"))
    )
    (net (code "28") (name "DATA3") (class "Default")
      (node (ref "U1") (pin "9") (pinfunction "4A_9") (pintype "unspecified"))
    )
    (net (code "29") (name "DATA4") (class "Default")
      (node (ref "U1") (pin "11") (pinfunction "5A_11") (pintype "unspecified"))
    )
    (net (code "30") (name "DATA5") (class "Default")
      (node (ref "U1") (pin "13") (pinfunction "6A_13") (pintype "unspecified"))
    )
    (net (code "31") (name "DATA6") (class "Default")
      (node (ref "U2") (pin "1") (pinfunction "1A_1") (pintype "unspecified"))
    )
    (net (code "32") (name "DATA7") (class "Default")
      (node (ref "U2") (pin "3") (pinfunction "2A_3") (pintype "unspecified"))
    )
    (net (code "33") (name "DATA8") (class "Default")
      (node (ref "U2") (pin "5") (pinfunction "3A_5") (pintype "unspecified"))
    )
    (net (code "34") (name "DATA9") (class "Default")
      (node (ref "U2") (pin "9") (pinfunction "4A_9") (pintype "unspecified"))
    )
    (net (code "35") (name "DATA10") (class "Default")
      (node (ref "U2") (pin "11") (pinfunction "5A_11") (pintype "unspecified"))
    )
    (net (code "36") (name "DATA11") (class "Default")
      (node (ref "U2") (pin "13") (pinfunction "6A_13") (pintype "unspecified"))
    )
    (net (code "37") (name "DATA12") (class "Default")
      (node (ref "U3") (pin "1") (pinfunction "1A_1") (pintype "unspecified"))
    )
    (net (code "38") (name "DATA13") (class "Default")
      (node (ref "U3") (pin "3") (pinfunction "2A_3") (pintype "unspecified"))
    )
    (net (code "39") (name "DATA14") (class "Default")
      (node (ref "U3") (pin "5") (pinfunction "3A_5") (pintype "unspecified"))
    )
    (net (code "40") (name "DATA15") (class "Default")
      (node (ref "U3") (pin "9") (pinfunction "4A_9") (pintype "unspecified"))
    )
    (net (code "41") (name "DATOA") (class "Default")
      (node (ref "R4") (pin "1") (pinfunction "1_1") (pintype "unspecified"))
      (node (ref "U6") (pin "1") (pinfunction "1A_1") (pintype "unspecified"))
    )
    (net (code "42") (name "DATOB") (class "Default")
      (node (ref "R5") (pin "1") (pinfunction "1_1") (pintype "unspecified"))
      (node (ref "U6") (pin "4") (pinfunction "2A_4") (pintype "unspecified"))
    )
    (net (code "43") (name "DS0") (class "Default")
      (node (ref "U4") (pin "1") (pinfunction "A_1") (pintype "unspecified"))
    )
    (net (code "44") (name "DS1") (class "Default")
      (node (ref "U5") (pin "1") (pinfunction "1A_1") (pintype "unspecified"))
    )
    (net (code "45") (name "DS2") (class "Default")
      (node (ref "U4") (pin "3") (pinfunction "C_3") (pintype "unspecified"))
    )
    (net (code "46") (name "DS3") (class "Default")
      (node (ref "U4") (pin "4") (pinfunction "D_4") (pintype "unspecified"))
    )
    (net (code "47") (name "DS4") (class "Default")
      (node (ref "U5") (pin "3") (pinfunction "2A_3") (pintype "unspecified"))
    )
    (net (code "48") (name "DS5") (class "Default")
      (node (ref "U5") (pin "5") (pinfunction "3A_5") (pintype "unspecified"))
    )
    (net (code "49") (name "GND") (class "Default")
      (node (ref "C1") (pin "1") (pinfunction "1_1") (pintype "unspecified"))
      (node (ref "C12") (pin "1") (pinfunction "1_1") (pintype "unspecified"))
      (node (ref "C13") (pin "1") (pinfunction "1_1") (pintype "unspecified"))
      (node (ref "C14") (pin "1") (pinfunction "1_1") (pintype "unspecified"))
      (node (ref "C15") (pin "1") (pinfunction "1_1") (pintype "unspecified"))
      (node (ref "C16") (pin "1") (pinfunction "1_1") (pintype "unspecified"))
      (node (ref "C17") (pin "1") (pinfunction "1_1") (pintype "unspecified"))
      (node (ref "C18") (pin "2") (pinfunction "2_2") (pintype "input"))
      (node (ref "C19") (pin "1") (pinfunction "1_1") (pintype "unspecified"))
      (node (ref "C2") (pin "1") (pinfunction "1_1") (pintype "unspecified"))
      (node (ref "C20") (pin "1") (pinfunction "1_1") (pintype "unspecified"))
      (node (ref "C21") (pin "1") (pinfunction "1_1") (pintype "unspecified"))
      (node (ref "C22") (pin "1") (pinfunction "1_1") (pintype "unspecified"))
      (node (ref "C23") (pin "1") (pinfunction "1_1") (pintype "unspecified"))
      (node (ref "C24") (pin "1") (pinfunction "1_1") (pintype "unspecified"))
      (node (ref "C25") (pin "2") (pinfunction "2_2") (pintype "input"))
      (node (ref "C26") (pin "1") (pinfunction "1_1") (pintype "unspecified"))
      (node (ref "C27") (pin "1") (pinfunction "1_1") (pintype "unspecified"))
      (node (ref "C28") (pin "1") (pinfunction "1_1") (pintype "unspecified"))
      (node (ref "C29") (pin "1") (pinfunction "1_1") (pintype "unspecified"))
      (node (ref "C3") (pin "1") (pinfunction "1_1") (pintype "unspecified"))
      (node (ref "C30") (pin "1") (pinfunction "1_1") (pintype "unspecified"))
      (node (ref "C31") (pin "1") (pinfunction "1_1") (pintype "unspecified"))
      (node (ref "C4") (pin "1") (pinfunction "1_1") (pintype "unspecified"))
      (node (ref "C5") (pin "1") (pinfunction "1_1") (pintype "unspecified"))
      (node (ref "C6") (pin "1") (pinfunction "1_1") (pintype "unspecified"))
      (node (ref "C7") (pin "1") (pinfunction "1_1") (pintype "unspecified"))
      (node (ref "C8") (pin "1") (pinfunction "1_1") (pintype "unspecified"))
      (node (ref "C9") (pin "1") (pinfunction "1_1") (pintype "unspecified"))
      (node (ref "CN1") (pin "10") (pinfunction "10_10") (pintype "unspecified"))
      (node (ref "CN1") (pin "12") (pinfunction "12_12") (pintype "unspecified"))
      (node (ref "CN1") (pin "14") (pinfunction "14_14") (pintype "unspecified"))
      (node (ref "CN1") (pin "16") (pinfunction "16_16") (pintype "unspecified"))
      (node (ref "CN1") (pin "2") (pinfunction "2_2") (pintype "unspecified"))
      (node (ref "CN1") (pin "4") (pinfunction "4_4") (pintype "unspecified"))
      (node (ref "CN1") (pin "6") (pinfunction "6_6") (pintype "unspecified"))
      (node (ref "CN1") (pin "8") (pinfunction "8_8") (pintype "unspecified"))
      (node (ref "CN2") (pin "10") (pinfunction "10_10") (pintype "unspecified"))
      (node (ref "CN2") (pin "12") (pinfunction "12_12") (pintype "unspecified"))
      (node (ref "CN2") (pin "14") (pinfunction "14_14") (pintype "unspecified"))
      (node (ref "CN2") (pin "16") (pinfunction "16_16") (pintype "unspecified"))
      (node (ref "CN2") (pin "2") (pinfunction "2_2") (pintype "unspecified"))
      (node (ref "CN2") (pin "4") (pinfunction "4_4") (pintype "unspecified"))
      (node (ref "CN2") (pin "6") (pinfunction "6_6") (pintype "unspecified"))
      (node (ref "CN2") (pin "8") (pinfunction "8_8") (pintype "unspecified"))
      (node (ref "CN3") (pin "10") (pinfunction "10_10") (pintype "unspecified"))
      (node (ref "CN3") (pin "12") (pinfunction "12_12") (pintype "unspecified"))
      (node (ref "CN3") (pin "14") (pinfunction "14_14") (pintype "unspecified"))
      (node (ref "CN3") (pin "16") (pinfunction "16_16") (pintype "unspecified"))
      (node (ref "CN3") (pin "2") (pinfunction "2_2") (pintype "unspecified"))
      (node (ref "CN3") (pin "4") (pinfunction "4_4") (pintype "unspecified"))
      (node (ref "CN3") (pin "6") (pinfunction "6_6") (pintype "unspecified"))
      (node (ref "CN3") (pin "8") (pinfunction "8_8") (pintype "unspecified"))
      (node (ref "CN4") (pin "10") (pinfunction "10_10") (pintype "unspecified"))
      (node (ref "CN4") (pin "12") (pinfunction "12_12") (pintype "unspecified"))
      (node (ref "CN4") (pin "14") (pinfunction "14_14") (pintype "unspecified"))
      (node (ref "CN4") (pin "16") (pinfunction "16_16") (pintype "unspecified"))
      (node (ref "CN4") (pin "2") (pinfunction "2_2") (pintype "unspecified"))
      (node (ref "CN4") (pin "4") (pinfunction "4_4") (pintype "unspecified"))
      (node (ref "CN4") (pin "6") (pinfunction "6_6") (pintype "unspecified"))
      (node (ref "CN4") (pin "8") (pinfunction "8_8") (pintype "unspecified"))
      (node (ref "J1") (pin "1") (pinfunction "1_1") (pintype "input"))
      (node (ref "J2") (pin "1") (pinfunction "1_1") (pintype "input"))
      (node (ref "J3") (pin "1") (pinfunction "1_1") (pintype "input"))
      (node (ref "J4") (pin "1") (pinfunction "1_1") (pintype "input"))
      (node (ref "J5") (pin "1") (pinfunction "1_1") (pintype "input"))
      (node (ref "J6") (pin "1") (pinfunction "1_1") (pintype "input"))
      (node (ref "J7") (pin "1") (pinfunction "1_1") (pintype "input"))
      (node (ref "R2") (pin "1") (pinfunction "1_1") (pintype "unspecified"))
      (node (ref "U1") (pin "7") (pinfunction "GND_7") (pintype "unspecified"))
      (node (ref "U10") (pin "1") (pinfunction "OC#_1") (pintype "input"))
      (node (ref "U10") (pin "10") (pinfunction "GND_10") (pintype "input"))
      (node (ref "U11") (pin "1") (pinfunction "OC#_1") (pintype "input"))
      (node (ref "U11") (pin "10") (pinfunction "GND_10") (pintype "input"))
      (node (ref "U12") (pin "1") (pinfunction "OC#_1") (pintype "input"))
      (node (ref "U12") (pin "10") (pinfunction "GND_10") (pintype "input"))
      (node (ref "U13") (pin "19") (pinfunction "WR#_19") (pintype "unspecified"))
      (node (ref "U13") (pin "2") (pinfunction "ROFSB_2") (pintype "unspecified"))
      (node (ref "U13") (pin "22") (pinfunction "VSS_22") (pintype "unspecified"))
      (node (ref "U13") (pin "23") (pinfunction "ROFSA_23") (pintype "unspecified"))
      (node (ref "U13") (pin "6") (pinfunction "GND_6") (pintype "unspecified"))
      (node (ref "U14") (pin "19") (pinfunction "WR#_19") (pintype "unspecified"))
      (node (ref "U14") (pin "2") (pinfunction "ROFSB_2") (pintype "unspecified"))
      (node (ref "U14") (pin "22") (pinfunction "VSS_22") (pintype "unspecified"))
      (node (ref "U14") (pin "23") (pinfunction "ROFSA_23") (pintype "unspecified"))
      (node (ref "U14") (pin "6") (pinfunction "GND_6") (pintype "unspecified"))
      (node (ref "U15") (pin "19") (pinfunction "WR#_19") (pintype "unspecified"))
      (node (ref "U15") (pin "2") (pinfunction "ROFSB_2") (pintype "unspecified"))
      (node (ref "U15") (pin "22") (pinfunction "VSS_22") (pintype "unspecified"))
      (node (ref "U15") (pin "23") (pinfunction "ROFSA_23") (pintype "unspecified"))
      (node (ref "U15") (pin "6") (pinfunction "GND_6") (pintype "unspecified"))
      (node (ref "U16") (pin "4") (pinfunction "V-_4") (pintype "unspecified"))
      (node (ref "U17") (pin "4") (pinfunction "V-_4") (pintype "unspecified"))
      (node (ref "U18") (pin "4") (pinfunction "V-_4") (pintype "unspecified"))
      (node (ref "U19") (pin "1") (pinfunction "A1_1") (pintype "unspecified"))
      (node (ref "U19") (pin "2") (pinfunction "A2_2") (pintype "unspecified"))
      (node (ref "U19") (pin "7") (pinfunction "GND_7") (pintype "unspecified"))
      (node (ref "U2") (pin "7") (pinfunction "GND_7") (pintype "unspecified"))
      (node (ref "U20") (pin "1") (pinfunction "A1_1") (pintype "unspecified"))
      (node (ref "U20") (pin "2") (pinfunction "A2_2") (pintype "unspecified"))
      (node (ref "U20") (pin "7") (pinfunction "GND_7") (pintype "unspecified"))
      (node (ref "U3") (pin "7") (pinfunction "GND_7") (pintype "unspecified"))
      (node (ref "U4") (pin "7") (pinfunction "GND_7") (pintype "unspecified"))
      (node (ref "U5") (pin "7") (pinfunction "GND_7") (pintype "unspecified"))
      (node (ref "U6") (pin "7") (pinfunction "GND_7") (pintype "unspecified"))
      (node (ref "U7") (pin "12") (pinfunction "GND_12") (pintype "input"))
      (node (ref "U7") (pin "7") (pinfunction "4D_7") (pintype "input"))
      (node (ref "U8") (pin "5") (pinfunction "G#2B_5") (pintype "input"))
      (node (ref "U8") (pin "8") (pinfunction "GND_8") (pintype "input"))
      (node (ref "U9") (pin "1") (pinfunction "OC#_1") (pintype "input"))
      (node (ref "U9") (pin "10") (pinfunction "GND_10") (pintype "input"))
    )
    (net (code "50") (name "Net-(H1-Pad2)") (class "Default")
      (node (ref "H1") (pin "2") (pinfunction "2_2") (pintype "unspecified"))
      (node (ref "J7") (pin "3") (pinfunction "3_3") (pintype "input"))
    )
    (net (code "51") (name "Net-(R12-Pad2)") (class "Default")
      (node (ref "R12") (pin "2") (pinfunction "2_2") (pintype "unspecified"))
      (node (ref "VR1") (pin "3") (pinfunction "3_3") (pintype "input"))
    )
    (net (code "52") (name "Net-(R13-Pad2)") (class "Default")
      (node (ref "R13") (pin "2") (pinfunction "2_2") (pintype "unspecified"))
      (node (ref "VR2") (pin "3") (pinfunction "3_3") (pintype "input"))
    )
    (net (code "53") (name "Net-(U4-B)") (class "Default")
      (node (ref "U4") (pin "2") (pinfunction "B_2") (pintype "unspecified"))
      (node (ref "U5") (pin "2") (pinfunction "1Y_2") (pintype "unspecified"))
    )
    (net (code "54") (name "Net-(U4-E)") (class "Default")
      (node (ref "U4") (pin "5") (pinfunction "E_5") (pintype "unspecified"))
      (node (ref "U5") (pin "4") (pinfunction "2Y_4") (pintype "unspecified"))
    )
    (net (code "55") (name "Net-(U4-F)") (class "Default")
      (node (ref "U4") (pin "6") (pinfunction "F_6") (pintype "unspecified"))
      (node (ref "U5") (pin "6") (pinfunction "3Y_6") (pintype "unspecified"))
    )
    (net (code "56") (name "Net-(U4-Y)") (class "Default")
      (node (ref "U4") (pin "8") (pinfunction "Y_8") (pintype "unspecified"))
      (node (ref "U5") (pin "13") (pinfunction "6A_13") (pintype "unspecified"))
      (node (ref "U8") (pin "4") (pinfunction "G#2A_4") (pintype "input"))
    )
    (net (code "57") (name "Net-(U5-4A)") (class "Default")
      (node (ref "U5") (pin "9") (pinfunction "4A_9") (pintype "unspecified"))
      (node (ref "U8") (pin "9") (pinfunction "Y6_9") (pintype "input"))
    )
    (net (code "58") (name "Net-(U5-5A)") (class "Default")
      (node (ref "U5") (pin "11") (pinfunction "5A_11") (pintype "unspecified"))
      (node (ref "U8") (pin "7") (pinfunction "Y7_7") (pintype "input"))
    )
    (net (code "59") (name "Net-(U6-1B)") (class "Default")
      (node (ref "C2") (pin "2") (pinfunction "2_2") (pintype "unspecified"))
      (node (ref "R4") (pin "2") (pinfunction "2_2") (pintype "unspecified"))
      (node (ref "U6") (pin "2") (pinfunction "1B_2") (pintype "unspecified"))
    )
    (net (code "60") (name "Net-(U6-1Y)") (class "Default")
      (node (ref "U6") (pin "3") (pinfunction "1Y_3") (pintype "unspecified"))
      (node (ref "U8") (pin "6") (pinfunction "G1_6") (pintype "input"))
    )
    (net (code "61") (name "Net-(U6-2B)") (class "Default")
      (node (ref "C3") (pin "2") (pinfunction "2_2") (pintype "unspecified"))
      (node (ref "R5") (pin "2") (pinfunction "2_2") (pintype "unspecified"))
      (node (ref "U6") (pin "5") (pinfunction "2B_5") (pintype "unspecified"))
    )
    (net (code "62") (name "Net-(U6-2Y)") (class "Default")
      (node (ref "U6") (pin "10") (pinfunction "3B_10") (pintype "unspecified"))
      (node (ref "U6") (pin "6") (pinfunction "2Y_6") (pintype "unspecified"))
      (node (ref "U6") (pin "8") (pinfunction "3Y_8") (pintype "unspecified"))
      (node (ref "U7") (pin "13") (pinfunction "1C，2C_13") (pintype "input"))
      (node (ref "U7") (pin "4") (pinfunction "3C，4C_4") (pintype "input"))
    )
    (net (code "63") (name "Net-(U6-4B)") (class "Default")
      (node (ref "C1") (pin "2") (pinfunction "2_2") (pintype "unspecified"))
      (node (ref "R3") (pin "2") (pinfunction "2_2") (pintype "unspecified"))
      (node (ref "U6") (pin "13") (pinfunction "4B_13") (pintype "unspecified"))
    )
    (net (code "64") (name "Net-(U7-1Q)") (class "Default")
      (node (ref "U7") (pin "16") (pinfunction "1Q_16") (pintype "input"))
      (node (ref "U8") (pin "1") (pinfunction "A_1") (pintype "input"))
    )
    (net (code "65") (name "Net-(U7-2Q)") (class "Default")
      (node (ref "U7") (pin "15") (pinfunction "2Q_15") (pintype "input"))
      (node (ref "U8") (pin "2") (pinfunction "B_2") (pintype "input"))
    )
    (net (code "66") (name "Net-(U7-3Q)") (class "Default")
      (node (ref "U7") (pin "10") (pinfunction "3Q_10") (pintype "input"))
      (node (ref "U8") (pin "3") (pinfunction "C_3") (pintype "input"))
    )
    (net (code "67") (name "Net-(U13-REF_IN)") (class "Default")
      (node (ref "U13") (pin "1") (pinfunction "REF_OUT_1") (pintype "unspecified"))
      (node (ref "U13") (pin "24") (pinfunction "REF_IN_24") (pintype "unspecified"))
    )
    (net (code "68") (name "Net-(U13-VOUTA)") (class "Default")
      (node (ref "R7") (pin "1") (pinfunction "1_1") (pintype "unspecified"))
      (node (ref "U13") (pin "21") (pinfunction "VOUTA_21") (pintype "unspecified"))
    )
    (net (code "69") (name "Net-(U13-VOUTB)") (class "Default")
      (node (ref "R6") (pin "1") (pinfunction "1_1") (pintype "unspecified"))
      (node (ref "U13") (pin "3") (pinfunction "VOUTB_3") (pintype "unspecified"))
    )
    (net (code "70") (name "Net-(U14-REF_IN)") (class "Default")
      (node (ref "U14") (pin "1") (pinfunction "REF_OUT_1") (pintype "unspecified"))
      (node (ref "U14") (pin "24") (pinfunction "REF_IN_24") (pintype "unspecified"))
    )
    (net (code "71") (name "Net-(U14-VOUTA)") (class "Default")
      (node (ref "R9") (pin "1") (pinfunction "1_1") (pintype "unspecified"))
      (node (ref "U14") (pin "21") (pinfunction "VOUTA_21") (pintype "unspecified"))
    )
    (net (code "72") (name "Net-(U14-VOUTB)") (class "Default")
      (node (ref "R8") (pin "1") (pinfunction "1_1") (pintype "unspecified"))
      (node (ref "U14") (pin "3") (pinfunction "VOUTB_3") (pintype "unspecified"))
    )
    (net (code "73") (name "Net-(U15-REF_IN)") (class "Default")
      (node (ref "U15") (pin "1") (pinfunction "REF_OUT_1") (pintype "unspecified"))
      (node (ref "U15") (pin "24") (pinfunction "REF_IN_24") (pintype "unspecified"))
    )
    (net (code "74") (name "Net-(U15-VOUTA)") (class "Default")
      (node (ref "R11") (pin "1") (pinfunction "1_1") (pintype "unspecified"))
      (node (ref "U15") (pin "21") (pinfunction "VOUTA_21") (pintype "unspecified"))
    )
    (net (code "75") (name "Net-(U15-VOUTB)") (class "Default")
      (node (ref "R10") (pin "1") (pinfunction "1_1") (pintype "unspecified"))
      (node (ref "U15") (pin "3") (pinfunction "VOUTB_3") (pintype "unspecified"))
    )
    (net (code "76") (name "Net-(U16A-INA+)") (class "Default")
      (node (ref "C4") (pin "2") (pinfunction "2_2") (pintype "unspecified"))
      (node (ref "R6") (pin "2") (pinfunction "2_2") (pintype "unspecified"))
      (node (ref "U16") (pin "3") (pinfunction "INA+_3") (pintype "input"))
    )
    (net (code "77") (name "Net-(U16A-INA-)") (class "Default")
      (node (ref "J1") (pin "3") (pinfunction "3_3") (pintype "input"))
      (node (ref "U16") (pin "1") (pinfunction "OUTA_1") (pintype "output"))
      (node (ref "U16") (pin "2") (pinfunction "INA-_2") (pintype "input"))
    )
    (net (code "78") (name "Net-(U16B-+INB)") (class "Default")
      (node (ref "C5") (pin "2") (pinfunction "2_2") (pintype "unspecified"))
      (node (ref "R7") (pin "2") (pinfunction "2_2") (pintype "unspecified"))
      (node (ref "U16") (pin "5") (pinfunction "+INB_5") (pintype "input"))
    )
    (net (code "79") (name "Net-(U16B--INB)") (class "Default")
      (node (ref "J2") (pin "3") (pinfunction "3_3") (pintype "input"))
      (node (ref "U16") (pin "6") (pinfunction "-INB_6") (pintype "input"))
      (node (ref "U16") (pin "7") (pinfunction "OUTB_7") (pintype "output"))
    )
    (net (code "80") (name "Net-(U17A-INA+)") (class "Default")
      (node (ref "C6") (pin "2") (pinfunction "2_2") (pintype "unspecified"))
      (node (ref "R8") (pin "2") (pinfunction "2_2") (pintype "unspecified"))
      (node (ref "U17") (pin "3") (pinfunction "INA+_3") (pintype "input"))
    )
    (net (code "81") (name "Net-(U17A-INA-)") (class "Default")
      (node (ref "J3") (pin "3") (pinfunction "3_3") (pintype "input"))
      (node (ref "U17") (pin "1") (pinfunction "OUTA_1") (pintype "output"))
      (node (ref "U17") (pin "2") (pinfunction "INA-_2") (pintype "input"))
    )
    (net (code "82") (name "Net-(U17B-+INB)") (class "Default")
      (node (ref "C7") (pin "2") (pinfunction "2_2") (pintype "unspecified"))
      (node (ref "R9") (pin "2") (pinfunction "2_2") (pintype "unspecified"))
      (node (ref "U17") (pin "5") (pinfunction "+INB_5") (pintype "input"))
    )
    (net (code "83") (name "Net-(U17B--INB)") (class "Default")
      (node (ref "J4") (pin "3") (pinfunction "3_3") (pintype "input"))
      (node (ref "U17") (pin "6") (pinfunction "-INB_6") (pintype "input"))
      (node (ref "U17") (pin "7") (pinfunction "OUTB_7") (pintype "output"))
    )
    (net (code "84") (name "Net-(U18A-INA+)") (class "Default")
      (node (ref "C8") (pin "2") (pinfunction "2_2") (pintype "unspecified"))
      (node (ref "R10") (pin "2") (pinfunction "2_2") (pintype "unspecified"))
      (node (ref "U18") (pin "3") (pinfunction "INA+_3") (pintype "input"))
    )
    (net (code "85") (name "Net-(U18A-INA-)") (class "Default")
      (node (ref "J5") (pin "3") (pinfunction "3_3") (pintype "input"))
      (node (ref "U18") (pin "1") (pinfunction "OUTA_1") (pintype "output"))
      (node (ref "U18") (pin "2") (pinfunction "INA-_2") (pintype "input"))
    )
    (net (code "86") (name "Net-(U18B-+INB)") (class "Default")
      (node (ref "C9") (pin "2") (pinfunction "2_2") (pintype "unspecified"))
      (node (ref "R11") (pin "2") (pinfunction "2_2") (pintype "unspecified"))
      (node (ref "U18") (pin "5") (pinfunction "+INB_5") (pintype "input"))
    )
    (net (code "87") (name "Net-(U18B--INB)") (class "Default")
      (node (ref "J6") (pin "3") (pinfunction "3_3") (pintype "input"))
      (node (ref "U18") (pin "6") (pinfunction "-INB_6") (pintype "input"))
      (node (ref "U18") (pin "7") (pinfunction "OUTB_7") (pintype "output"))
    )
    (net (code "88") (name "Net-(U19-CEXT)") (class "Default")
      (node (ref "C10") (pin "1") (pinfunction "1_1") (pintype "unspecified"))
      (node (ref "U19") (pin "11") (pinfunction "CEXT_11") (pintype "unspecified"))
    )
    (net (code "89") (name "Net-(U19-Q#)") (class "Default")
      (node (ref "U19") (pin "6") (pinfunction "Q#_6") (pintype "unspecified"))
      (node (ref "U20") (pin "3") (pinfunction "B1_3") (pintype "unspecified"))
      (node (ref "U20") (pin "4") (pinfunction "B2_4") (pintype "unspecified"))
    )
    (net (code "90") (name "Net-(U19-REXT{slash}CEXT)") (class "Default")
      (node (ref "C10") (pin "2") (pinfunction "2_2") (pintype "unspecified"))
      (node (ref "R12") (pin "1") (pinfunction "1_1") (pintype "unspecified"))
      (node (ref "U19") (pin "13") (pinfunction "REXT/CEXT_13") (pintype "unspecified"))
    )
    (net (code "91") (name "Net-(U20-CEXT)") (class "Default")
      (node (ref "C11") (pin "1") (pinfunction "1_1") (pintype "unspecified"))
      (node (ref "U20") (pin "11") (pinfunction "CEXT_11") (pintype "unspecified"))
    )
    (net (code "92") (name "Net-(U20-Q#)") (class "Default")
      (node (ref "H1") (pin "3") (pinfunction "3_3") (pintype "unspecified"))
      (node (ref "U20") (pin "6") (pinfunction "Q#_6") (pintype "unspecified"))
    )
    (net (code "93") (name "Net-(U20-Q)") (class "Default")
      (node (ref "H1") (pin "1") (pinfunction "1_1") (pintype "unspecified"))
      (node (ref "U20") (pin "8") (pinfunction "Q_8") (pintype "unspecified"))
    )
    (net (code "94") (name "Net-(U20-REXT{slash}CEXT)") (class "Default")
      (node (ref "C11") (pin "2") (pinfunction "2_2") (pintype "unspecified"))
      (node (ref "R13") (pin "1") (pinfunction "1_1") (pintype "unspecified"))
      (node (ref "U20") (pin "13") (pinfunction "REXT/CEXT_13") (pintype "unspecified"))
    )
    (net (code "95") (name "PA0") (class "Default")
      (node (ref "CN1") (pin "1") (pinfunction "1_1") (pintype "unspecified"))
      (node (ref "U9") (pin "2") (pinfunction "1Q_2") (pintype "input"))
    )
    (net (code "96") (name "PA1") (class "Default")
      (node (ref "CN1") (pin "3") (pinfunction "3_3") (pintype "unspecified"))
      (node (ref "U9") (pin "5") (pinfunction "2Q_5") (pintype "input"))
    )
    (net (code "97") (name "PA2") (class "Default")
      (node (ref "CN1") (pin "5") (pinfunction "5_5") (pintype "unspecified"))
      (node (ref "U9") (pin "6") (pinfunction "3Q_6") (pintype "input"))
    )
    (net (code "98") (name "PA3") (class "Default")
      (node (ref "CN1") (pin "7") (pinfunction "7_7") (pintype "unspecified"))
      (node (ref "U9") (pin "9") (pinfunction "4Q_9") (pintype "input"))
    )
    (net (code "99") (name "PA4") (class "Default")
      (node (ref "CN1") (pin "9") (pinfunction "9_9") (pintype "unspecified"))
      (node (ref "U9") (pin "12") (pinfunction "5Q_12") (pintype "input"))
    )
    (net (code "100") (name "PA5") (class "Default")
      (node (ref "CN1") (pin "11") (pinfunction "11_11") (pintype "unspecified"))
      (node (ref "U9") (pin "15") (pinfunction "6Q_15") (pintype "input"))
    )
    (net (code "101") (name "PA6") (class "Default")
      (node (ref "CN1") (pin "13") (pinfunction "13_13") (pintype "unspecified"))
      (node (ref "U9") (pin "16") (pinfunction "7Q_16") (pintype "input"))
    )
    (net (code "102") (name "PA7") (class "Default")
      (node (ref "CN1") (pin "15") (pinfunction "15_15") (pintype "unspecified"))
      (node (ref "U9") (pin "19") (pinfunction "8Q_19") (pintype "input"))
    )
    (net (code "103") (name "PA8") (class "Default")
      (node (ref "CN2") (pin "1") (pinfunction "1_1") (pintype "unspecified"))
      (node (ref "U10") (pin "2") (pinfunction "1Q_2") (pintype "input"))
    )
    (net (code "104") (name "PA9") (class "Default")
      (node (ref "CN2") (pin "3") (pinfunction "3_3") (pintype "unspecified"))
      (node (ref "U10") (pin "5") (pinfunction "2Q_5") (pintype "input"))
    )
    (net (code "105") (name "PA10") (class "Default")
      (node (ref "CN2") (pin "5") (pinfunction "5_5") (pintype "unspecified"))
      (node (ref "U10") (pin "6") (pinfunction "3Q_6") (pintype "input"))
    )
    (net (code "106") (name "PA11") (class "Default")
      (node (ref "CN2") (pin "7") (pinfunction "7_7") (pintype "unspecified"))
      (node (ref "U10") (pin "9") (pinfunction "4Q_9") (pintype "input"))
    )
    (net (code "107") (name "PA12") (class "Default")
      (node (ref "CN2") (pin "9") (pinfunction "9_9") (pintype "unspecified"))
      (node (ref "U10") (pin "12") (pinfunction "5Q_12") (pintype "input"))
    )
    (net (code "108") (name "PA13") (class "Default")
      (node (ref "CN2") (pin "11") (pinfunction "11_11") (pintype "unspecified"))
      (node (ref "U10") (pin "15") (pinfunction "6Q_15") (pintype "input"))
    )
    (net (code "109") (name "PA14") (class "Default")
      (node (ref "CN2") (pin "13") (pinfunction "13_13") (pintype "unspecified"))
      (node (ref "U10") (pin "16") (pinfunction "7Q_16") (pintype "input"))
    )
    (net (code "110") (name "PA15") (class "Default")
      (node (ref "CN2") (pin "15") (pinfunction "15_15") (pintype "unspecified"))
      (node (ref "U10") (pin "19") (pinfunction "8Q_19") (pintype "input"))
    )
    (net (code "111") (name "PAWR") (class "Default")
      (node (ref "U10") (pin "11") (pinfunction "CLK_11") (pintype "input"))
      (node (ref "U5") (pin "8") (pinfunction "4Y_8") (pintype "unspecified"))
      (node (ref "U9") (pin "11") (pinfunction "CLK_11") (pintype "input"))
    )
    (net (code "112") (name "PB0") (class "Default")
      (node (ref "CN3") (pin "1") (pinfunction "1_1") (pintype "unspecified"))
      (node (ref "U11") (pin "2") (pinfunction "1Q_2") (pintype "input"))
    )
    (net (code "113") (name "PB1") (class "Default")
      (node (ref "CN3") (pin "3") (pinfunction "3_3") (pintype "unspecified"))
      (node (ref "U11") (pin "5") (pinfunction "2Q_5") (pintype "input"))
    )
    (net (code "114") (name "PB2") (class "Default")
      (node (ref "CN3") (pin "5") (pinfunction "5_5") (pintype "unspecified"))
      (node (ref "U11") (pin "6") (pinfunction "3Q_6") (pintype "input"))
    )
    (net (code "115") (name "PB3") (class "Default")
      (node (ref "CN3") (pin "7") (pinfunction "7_7") (pintype "unspecified"))
      (node (ref "U11") (pin "9") (pinfunction "4Q_9") (pintype "input"))
    )
    (net (code "116") (name "PB4") (class "Default")
      (node (ref "CN3") (pin "9") (pinfunction "9_9") (pintype "unspecified"))
      (node (ref "U11") (pin "12") (pinfunction "5Q_12") (pintype "input"))
    )
    (net (code "117") (name "PB5") (class "Default")
      (node (ref "CN3") (pin "11") (pinfunction "11_11") (pintype "unspecified"))
      (node (ref "U11") (pin "15") (pinfunction "6Q_15") (pintype "input"))
    )
    (net (code "118") (name "PB6") (class "Default")
      (node (ref "CN3") (pin "13") (pinfunction "13_13") (pintype "unspecified"))
      (node (ref "U11") (pin "16") (pinfunction "7Q_16") (pintype "input"))
    )
    (net (code "119") (name "PB7") (class "Default")
      (node (ref "CN3") (pin "15") (pinfunction "15_15") (pintype "unspecified"))
      (node (ref "U11") (pin "19") (pinfunction "8Q_19") (pintype "input"))
    )
    (net (code "120") (name "PB8") (class "Default")
      (node (ref "CN4") (pin "1") (pinfunction "1_1") (pintype "unspecified"))
      (node (ref "U12") (pin "2") (pinfunction "1Q_2") (pintype "input"))
    )
    (net (code "121") (name "PB9") (class "Default")
      (node (ref "CN4") (pin "3") (pinfunction "3_3") (pintype "unspecified"))
      (node (ref "U12") (pin "5") (pinfunction "2Q_5") (pintype "input"))
    )
    (net (code "122") (name "PB10") (class "Default")
      (node (ref "CN4") (pin "5") (pinfunction "5_5") (pintype "unspecified"))
      (node (ref "U12") (pin "6") (pinfunction "3Q_6") (pintype "input"))
    )
    (net (code "123") (name "PB11") (class "Default")
      (node (ref "CN4") (pin "7") (pinfunction "7_7") (pintype "unspecified"))
      (node (ref "U12") (pin "9") (pinfunction "4Q_9") (pintype "input"))
    )
    (net (code "124") (name "PB12") (class "Default")
      (node (ref "CN4") (pin "9") (pinfunction "9_9") (pintype "unspecified"))
      (node (ref "U12") (pin "12") (pinfunction "5Q_12") (pintype "input"))
    )
    (net (code "125") (name "PB13") (class "Default")
      (node (ref "CN4") (pin "11") (pinfunction "11_11") (pintype "unspecified"))
      (node (ref "U12") (pin "15") (pinfunction "6Q_15") (pintype "input"))
    )
    (net (code "126") (name "PB14") (class "Default")
      (node (ref "CN4") (pin "13") (pinfunction "13_13") (pintype "unspecified"))
      (node (ref "U12") (pin "16") (pinfunction "7Q_16") (pintype "input"))
    )
    (net (code "127") (name "PB15") (class "Default")
      (node (ref "CN4") (pin "15") (pinfunction "15_15") (pintype "unspecified"))
      (node (ref "U12") (pin "19") (pinfunction "8Q_19") (pintype "input"))
    )
    (net (code "128") (name "PBWR") (class "Default")
      (node (ref "U11") (pin "11") (pinfunction "CLK_11") (pintype "input"))
      (node (ref "U12") (pin "11") (pinfunction "CLK_11") (pintype "input"))
      (node (ref "U5") (pin "10") (pinfunction "5Y_10") (pintype "unspecified"))
    )
    (net (code "129") (name "START") (class "Default")
      (node (ref "U19") (pin "3") (pinfunction "B1_3") (pintype "unspecified"))
      (node (ref "U6") (pin "11") (pinfunction "4Y_11") (pintype "unspecified"))
    )
    (net (code "130") (name "STRT") (class "Default")
      (node (ref "R3") (pin "1") (pinfunction "1_1") (pintype "unspecified"))
      (node (ref "U6") (pin "12") (pinfunction "4A_12") (pintype "unspecified"))
    )
    (net (code "131") (name "VCC") (class "Default")
      (node (ref "C19") (pin "2") (pinfunction "2_2") (pintype "unspecified"))
      (node (ref "C20") (pin "2") (pinfunction "2_2") (pintype "unspecified"))
      (node (ref "C21") (pin "2") (pinfunction "2_2") (pintype "unspecified"))
      (node (ref "C22") (pin "2") (pinfunction "2_2") (pintype "unspecified"))
      (node (ref "C23") (pin "2") (pinfunction "2_2") (pintype "unspecified"))
      (node (ref "C24") (pin "2") (pinfunction "2_2") (pintype "unspecified"))
      (node (ref "C25") (pin "1") (pinfunction "1_1") (pintype "input"))
      (node (ref "C26") (pin "2") (pinfunction "2_2") (pintype "unspecified"))
      (node (ref "C27") (pin "2") (pinfunction "2_2") (pintype "unspecified"))
      (node (ref "C28") (pin "2") (pinfunction "2_2") (pintype "unspecified"))
      (node (ref "C29") (pin "2") (pinfunction "2_2") (pintype "unspecified"))
      (node (ref "C30") (pin "2") (pinfunction "2_2") (pintype "unspecified"))
      (node (ref "C31") (pin "2") (pinfunction "2_2") (pintype "unspecified"))
      (node (ref "R1") (pin "2") (pinfunction "2_2") (pintype "unspecified"))
      (node (ref "U1") (pin "14") (pinfunction "VCC_14") (pintype "unspecified"))
      (node (ref "U10") (pin "20") (pinfunction "VCC_20") (pintype "input"))
      (node (ref "U11") (pin "20") (pinfunction "VCC_20") (pintype "input"))
      (node (ref "U12") (pin "20") (pinfunction "VCC_20") (pintype "input"))
      (node (ref "U19") (pin "14") (pinfunction "VCC_14") (pintype "unspecified"))
      (node (ref "U2") (pin "14") (pinfunction "VCC_14") (pintype "unspecified"))
      (node (ref "U20") (pin "14") (pinfunction "VCC_14") (pintype "unspecified"))
      (node (ref "U3") (pin "14") (pinfunction "VCC_14") (pintype "unspecified"))
      (node (ref "U4") (pin "14") (pinfunction "VCC_14") (pintype "unspecified"))
      (node (ref "U5") (pin "14") (pinfunction "VCC_14") (pintype "unspecified"))
      (node (ref "U6") (pin "14") (pinfunction "VCC_14") (pintype "unspecified"))
      (node (ref "U7") (pin "5") (pinfunction "VCC_5") (pintype "input"))
      (node (ref "U8") (pin "16") (pinfunction "VCC_16") (pintype "input"))
      (node (ref "U9") (pin "20") (pinfunction "VCC_20") (pintype "input"))
      (node (ref "VR1") (pin "1") (pinfunction "1_1") (pintype "input"))
      (node (ref "VR1") (pin "2") (pinfunction "2_2") (pintype "input"))
      (node (ref "VR2") (pin "1") (pinfunction "1_1") (pintype "input"))
      (node (ref "VR2") (pin "2") (pinfunction "2_2") (pintype "input"))
    )
    (net (code "132") (name "VDD") (class "Default")
      (node (ref "C12") (pin "2") (pinfunction "2_2") (pintype "unspecified"))
      (node (ref "C13") (pin "2") (pinfunction "2_2") (pintype "unspecified"))
      (node (ref "C14") (pin "2") (pinfunction "2_2") (pintype "unspecified"))
      (node (ref "C15") (pin "2") (pinfunction "2_2") (pintype "unspecified"))
      (node (ref "C16") (pin "2") (pinfunction "2_2") (pintype "unspecified"))
      (node (ref "C17") (pin "2") (pinfunction "2_2") (pintype "unspecified"))
      (node (ref "C18") (pin "1") (pinfunction "1_1") (pintype "input"))
      (node (ref "U13") (pin "20") (pinfunction "VDD_20") (pintype "unspecified"))
      (node (ref "U14") (pin "20") (pinfunction "VDD_20") (pintype "unspecified"))
      (node (ref "U15") (pin "20") (pinfunction "VDD_20") (pintype "unspecified"))
      (node (ref "U16") (pin "8") (pinfunction "V+_8") (pintype "unspecified"))
      (node (ref "U17") (pin "8") (pinfunction "V+_8") (pintype "unspecified"))
      (node (ref "U18") (pin "8") (pinfunction "V+_8") (pintype "unspecified"))
    )
    (net (code "133") (name "unconnected-(J1-Pad2)") (class "Default")
      (node (ref "J1") (pin "2") (pinfunction "2_2") (pintype "input"))
    )
    (net (code "134") (name "unconnected-(J2-Pad2)") (class "Default")
      (node (ref "J2") (pin "2") (pinfunction "2_2") (pintype "input"))
    )
    (net (code "135") (name "unconnected-(J3-Pad2)") (class "Default")
      (node (ref "J3") (pin "2") (pinfunction "2_2") (pintype "input"))
    )
    (net (code "136") (name "unconnected-(J4-Pad2)") (class "Default")
      (node (ref "J4") (pin "2") (pinfunction "2_2") (pintype "input"))
    )
    (net (code "137") (name "unconnected-(J5-Pad2)") (class "Default")
      (node (ref "J5") (pin "2") (pinfunction "2_2") (pintype "input"))
    )
    (net (code "138") (name "unconnected-(J6-Pad2)") (class "Default")
      (node (ref "J6") (pin "2") (pinfunction "2_2") (pintype "input"))
    )
    (net (code "139") (name "unconnected-(J7-Pad2)") (class "Default")
      (node (ref "J7") (pin "2") (pinfunction "2_2") (pintype "input"))
    )
    (net (code "140") (name "unconnected-(U3-5A-Pad11)") (class "Default")
      (node (ref "U3") (pin "11") (pinfunction "5A_11") (pintype "unspecified"))
    )
    (net (code "141") (name "unconnected-(U3-5Y-Pad10)") (class "Default")
      (node (ref "U3") (pin "10") (pinfunction "5Y_10") (pintype "unspecified"))
    )
    (net (code "142") (name "unconnected-(U3-6A-Pad13)") (class "Default")
      (node (ref "U3") (pin "13") (pinfunction "6A_13") (pintype "unspecified"))
    )
    (net (code "143") (name "unconnected-(U3-6Y-Pad12)") (class "Default")
      (node (ref "U3") (pin "12") (pinfunction "6Y_12") (pintype "unspecified"))
    )
    (net (code "144") (name "unconnected-(U4-NC-Pad9)") (class "Default")
      (node (ref "U4") (pin "9") (pinfunction "NC_9") (pintype "unspecified"))
    )
    (net (code "145") (name "unconnected-(U4-NC-Pad10)") (class "Default")
      (node (ref "U4") (pin "10") (pinfunction "NC_10") (pintype "unspecified"))
    )
    (net (code "146") (name "unconnected-(U4-NC-Pad13)") (class "Default")
      (node (ref "U4") (pin "13") (pinfunction "NC_13") (pintype "unspecified"))
    )
    (net (code "147") (name "unconnected-(U7-1Q#-Pad1)") (class "Default")
      (node (ref "U7") (pin "1") (pinfunction "1Q#_1") (pintype "input"))
    )
    (net (code "148") (name "unconnected-(U7-2Q#-Pad14)") (class "Default")
      (node (ref "U7") (pin "14") (pinfunction "2Q#_14") (pintype "input"))
    )
    (net (code "149") (name "unconnected-(U7-3Q#-Pad11)") (class "Default")
      (node (ref "U7") (pin "11") (pinfunction "3Q#_11") (pintype "input"))
    )
    (net (code "150") (name "unconnected-(U7-4Q#-Pad8)") (class "Default")
      (node (ref "U7") (pin "8") (pinfunction "4Q#_8") (pintype "input"))
    )
    (net (code "151") (name "unconnected-(U7-4Q-Pad9)") (class "Default")
      (node (ref "U7") (pin "9") (pinfunction "4Q_9") (pintype "input"))
    )
    (net (code "152") (name "unconnected-(U19-NC-Pad10)") (class "Default")
      (node (ref "U19") (pin "10") (pinfunction "NC_10") (pintype "unspecified"))
    )
    (net (code "153") (name "unconnected-(U19-NC-Pad12)") (class "Default")
      (node (ref "U19") (pin "12") (pinfunction "NC_12") (pintype "unspecified"))
    )
    (net (code "154") (name "unconnected-(U19-Q-Pad8)") (class "Default")
      (node (ref "U19") (pin "8") (pinfunction "Q_8") (pintype "unspecified"))
    )
    (net (code "155") (name "unconnected-(U19-RINT-Pad9)") (class "Default")
      (node (ref "U19") (pin "9") (pinfunction "RINT_9") (pintype "unspecified"))
    )
    (net (code "156") (name "unconnected-(U20-NC-Pad10)") (class "Default")
      (node (ref "U20") (pin "10") (pinfunction "NC_10") (pintype "unspecified"))
    )
    (net (code "157") (name "unconnected-(U20-NC-Pad12)") (class "Default")
      (node (ref "U20") (pin "12") (pinfunction "NC_12") (pintype "unspecified"))
    )
    (net (code "158") (name "unconnected-(U20-RINT-Pad9)") (class "Default")
      (node (ref "U20") (pin "9") (pinfunction "RINT_9") (pintype "unspecified"))
    )
  )
)
